# power_supply_module.net
KiCad netlist of a schematic drawn in EAGLE
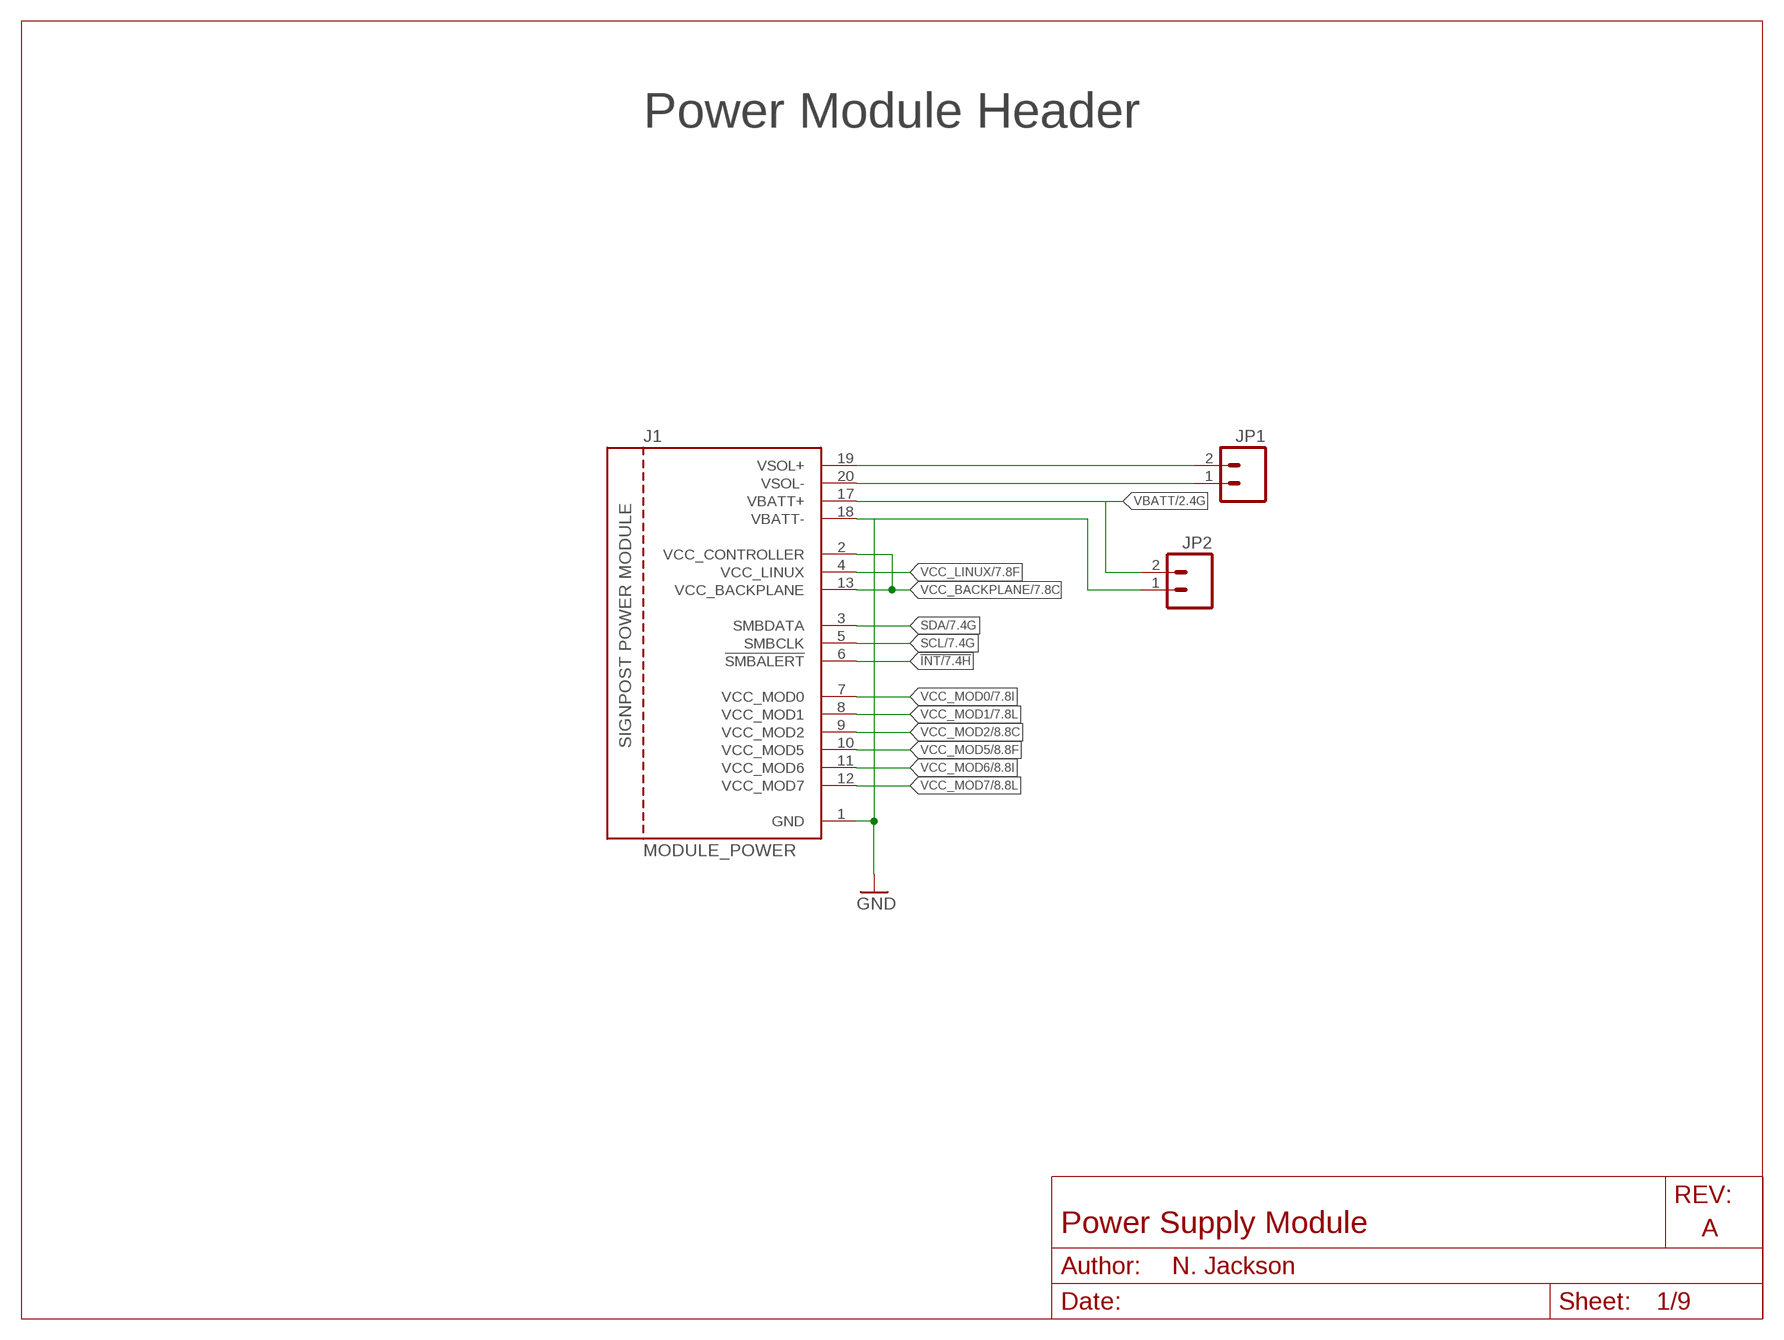
[diagram p0: schematic, sheet 1]
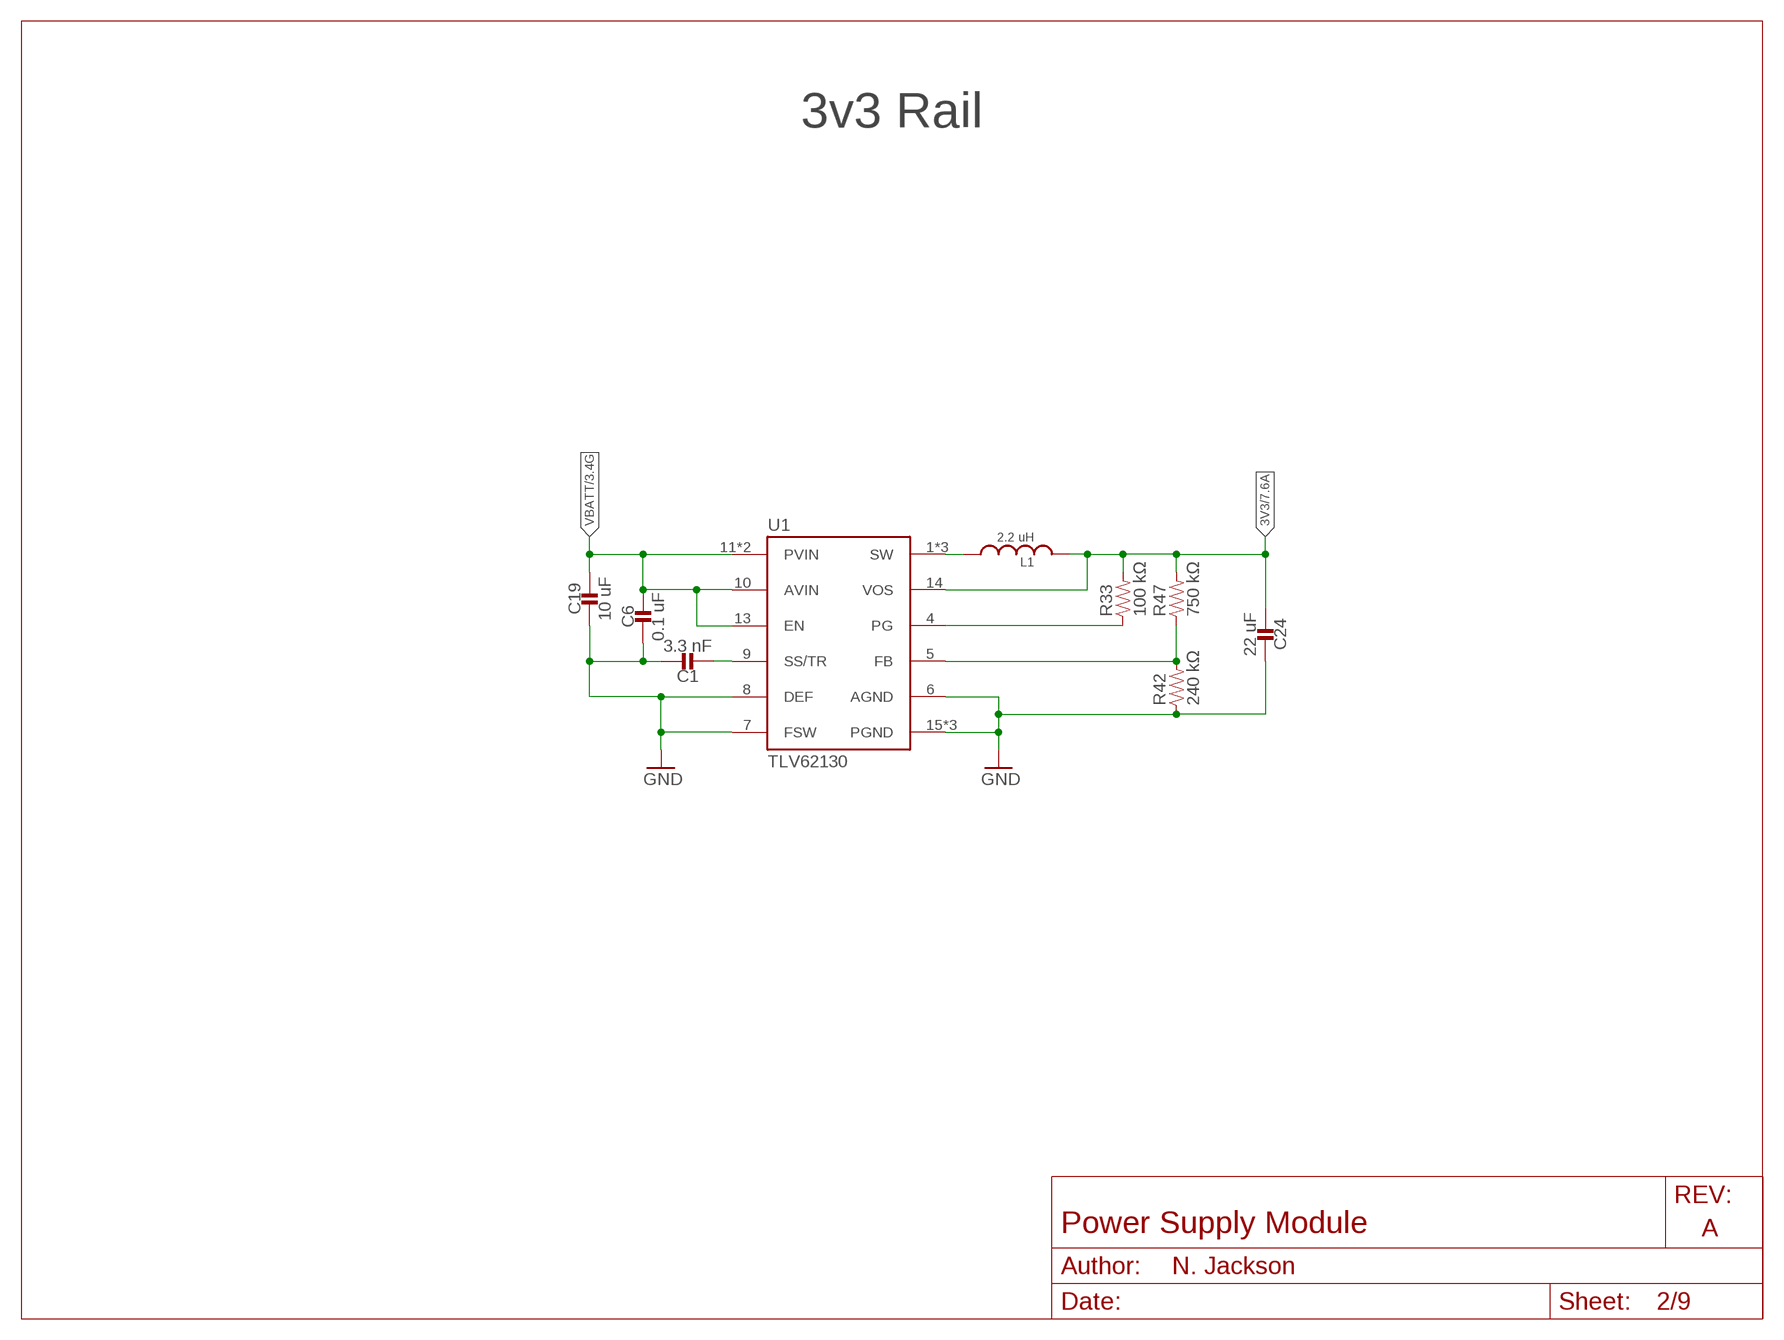
[diagram p1: schematic, sheet 2]
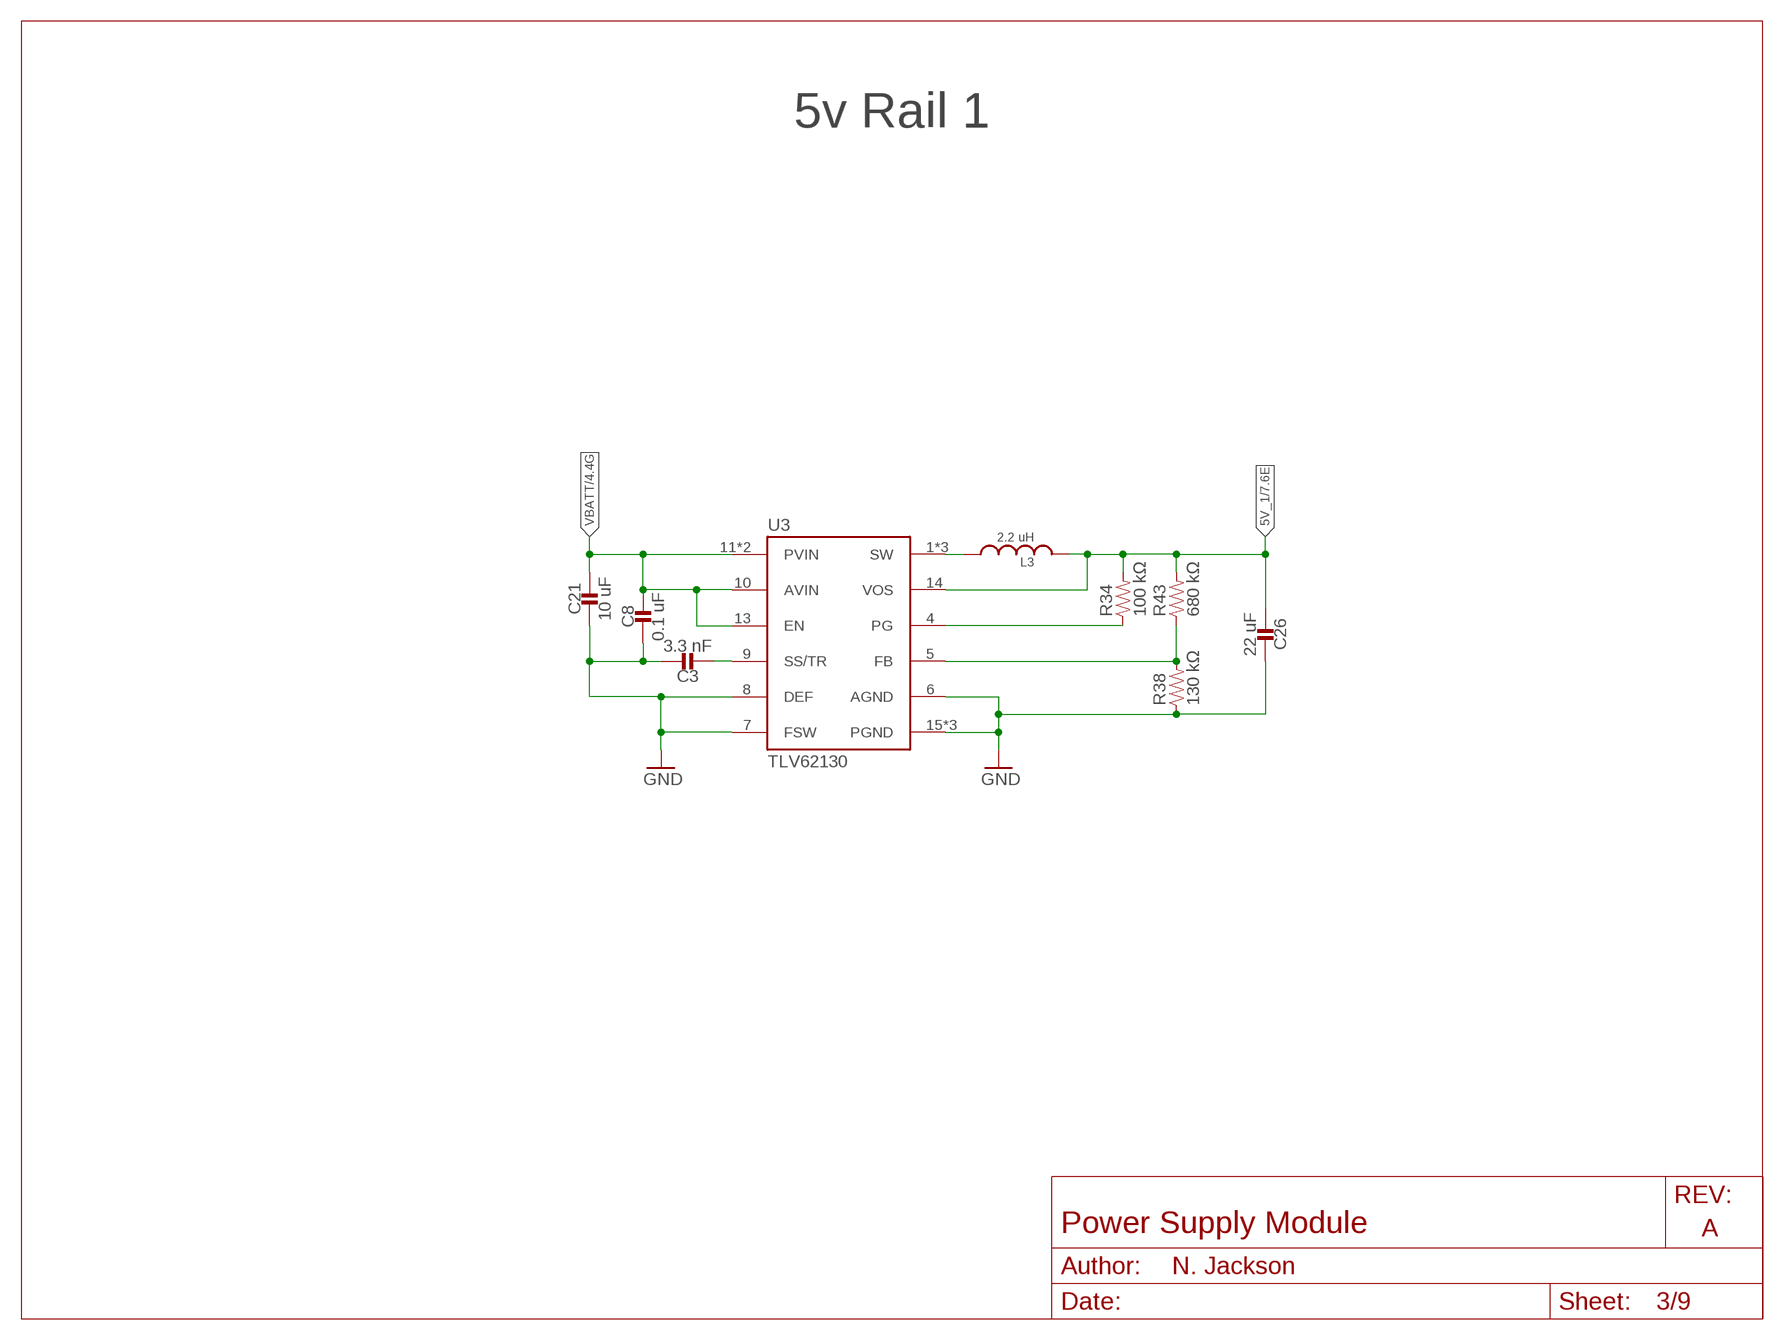
[diagram p2: schematic, sheet 3]
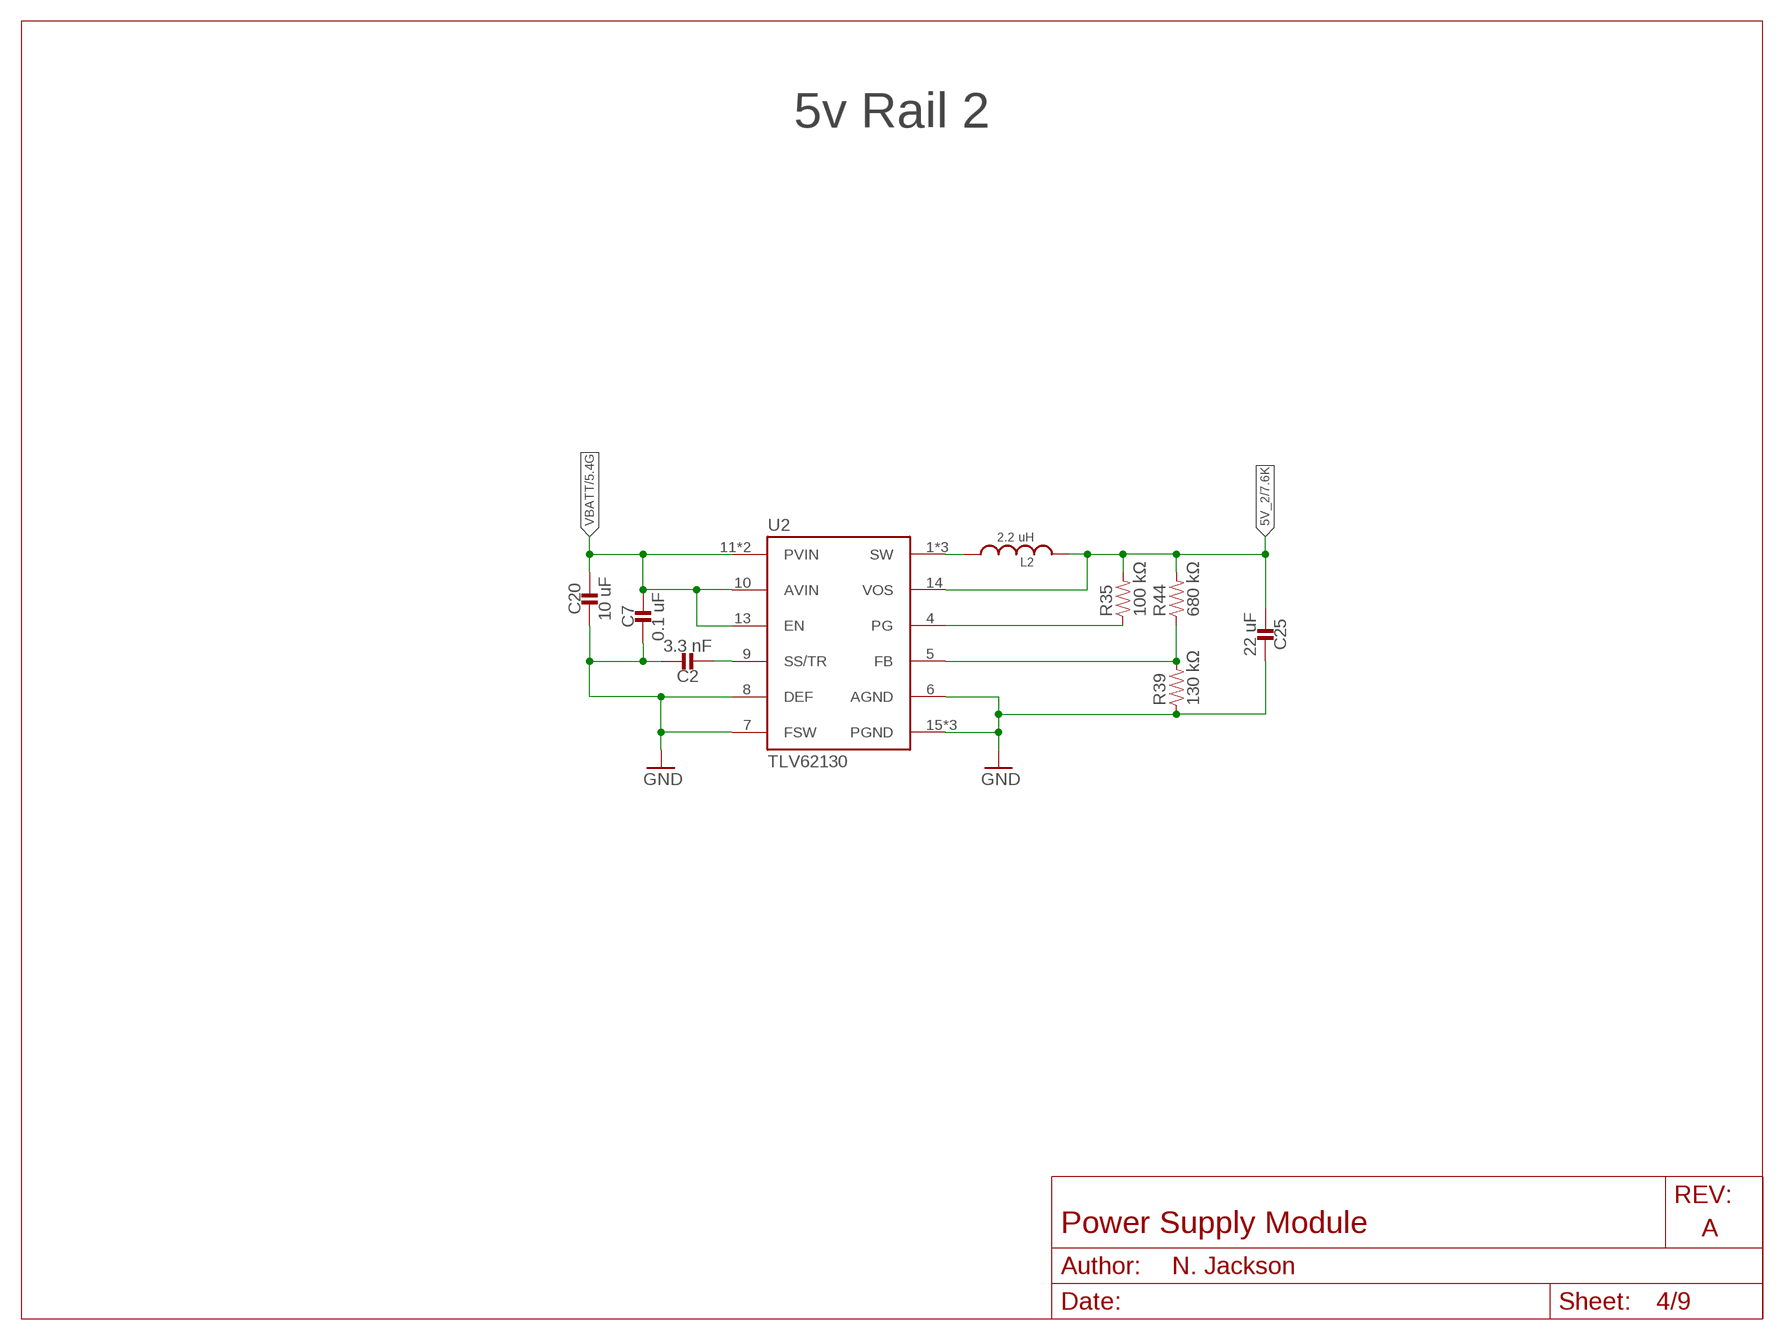
[diagram p3: schematic, sheet 4]
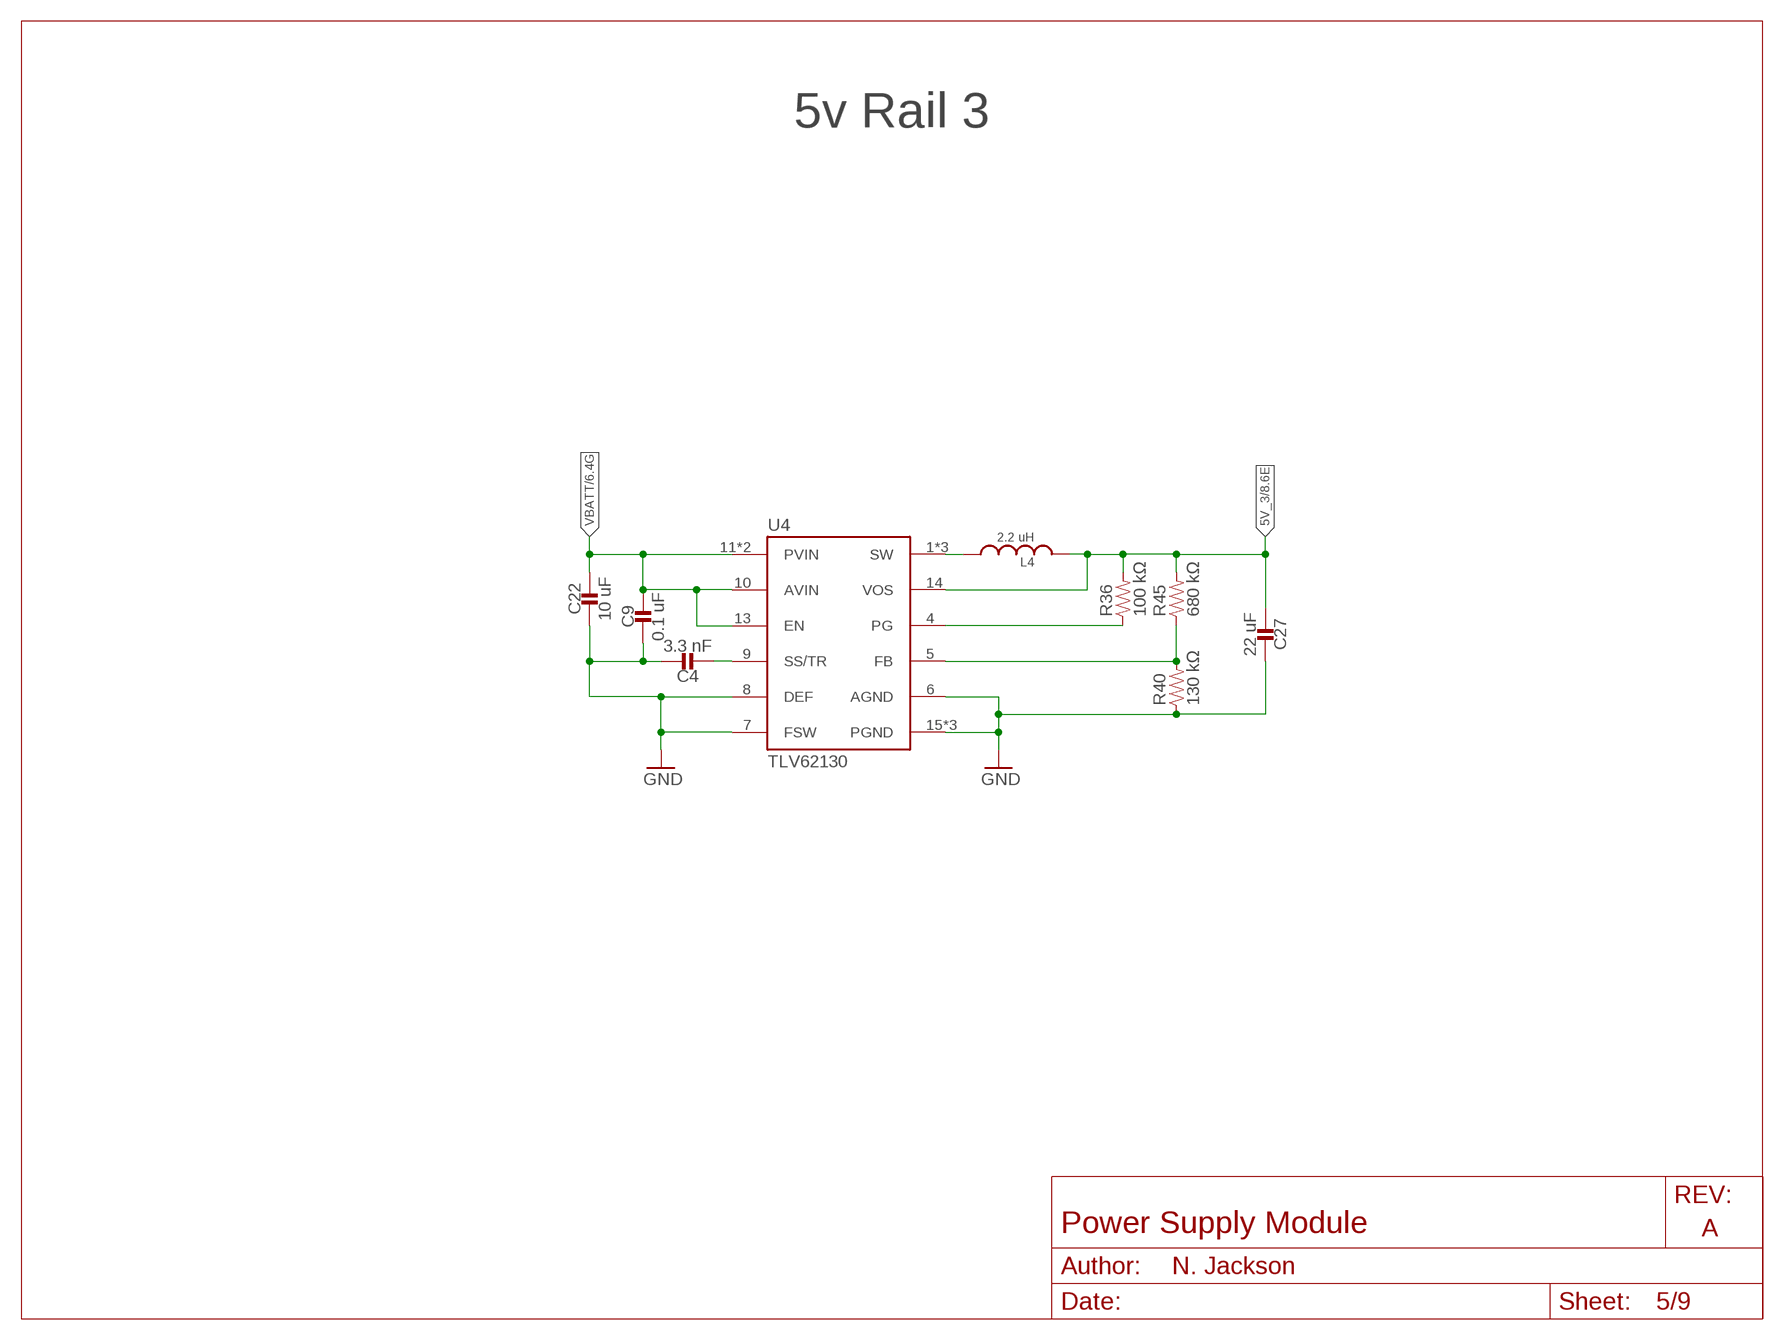
[diagram p4: schematic, sheet 5]
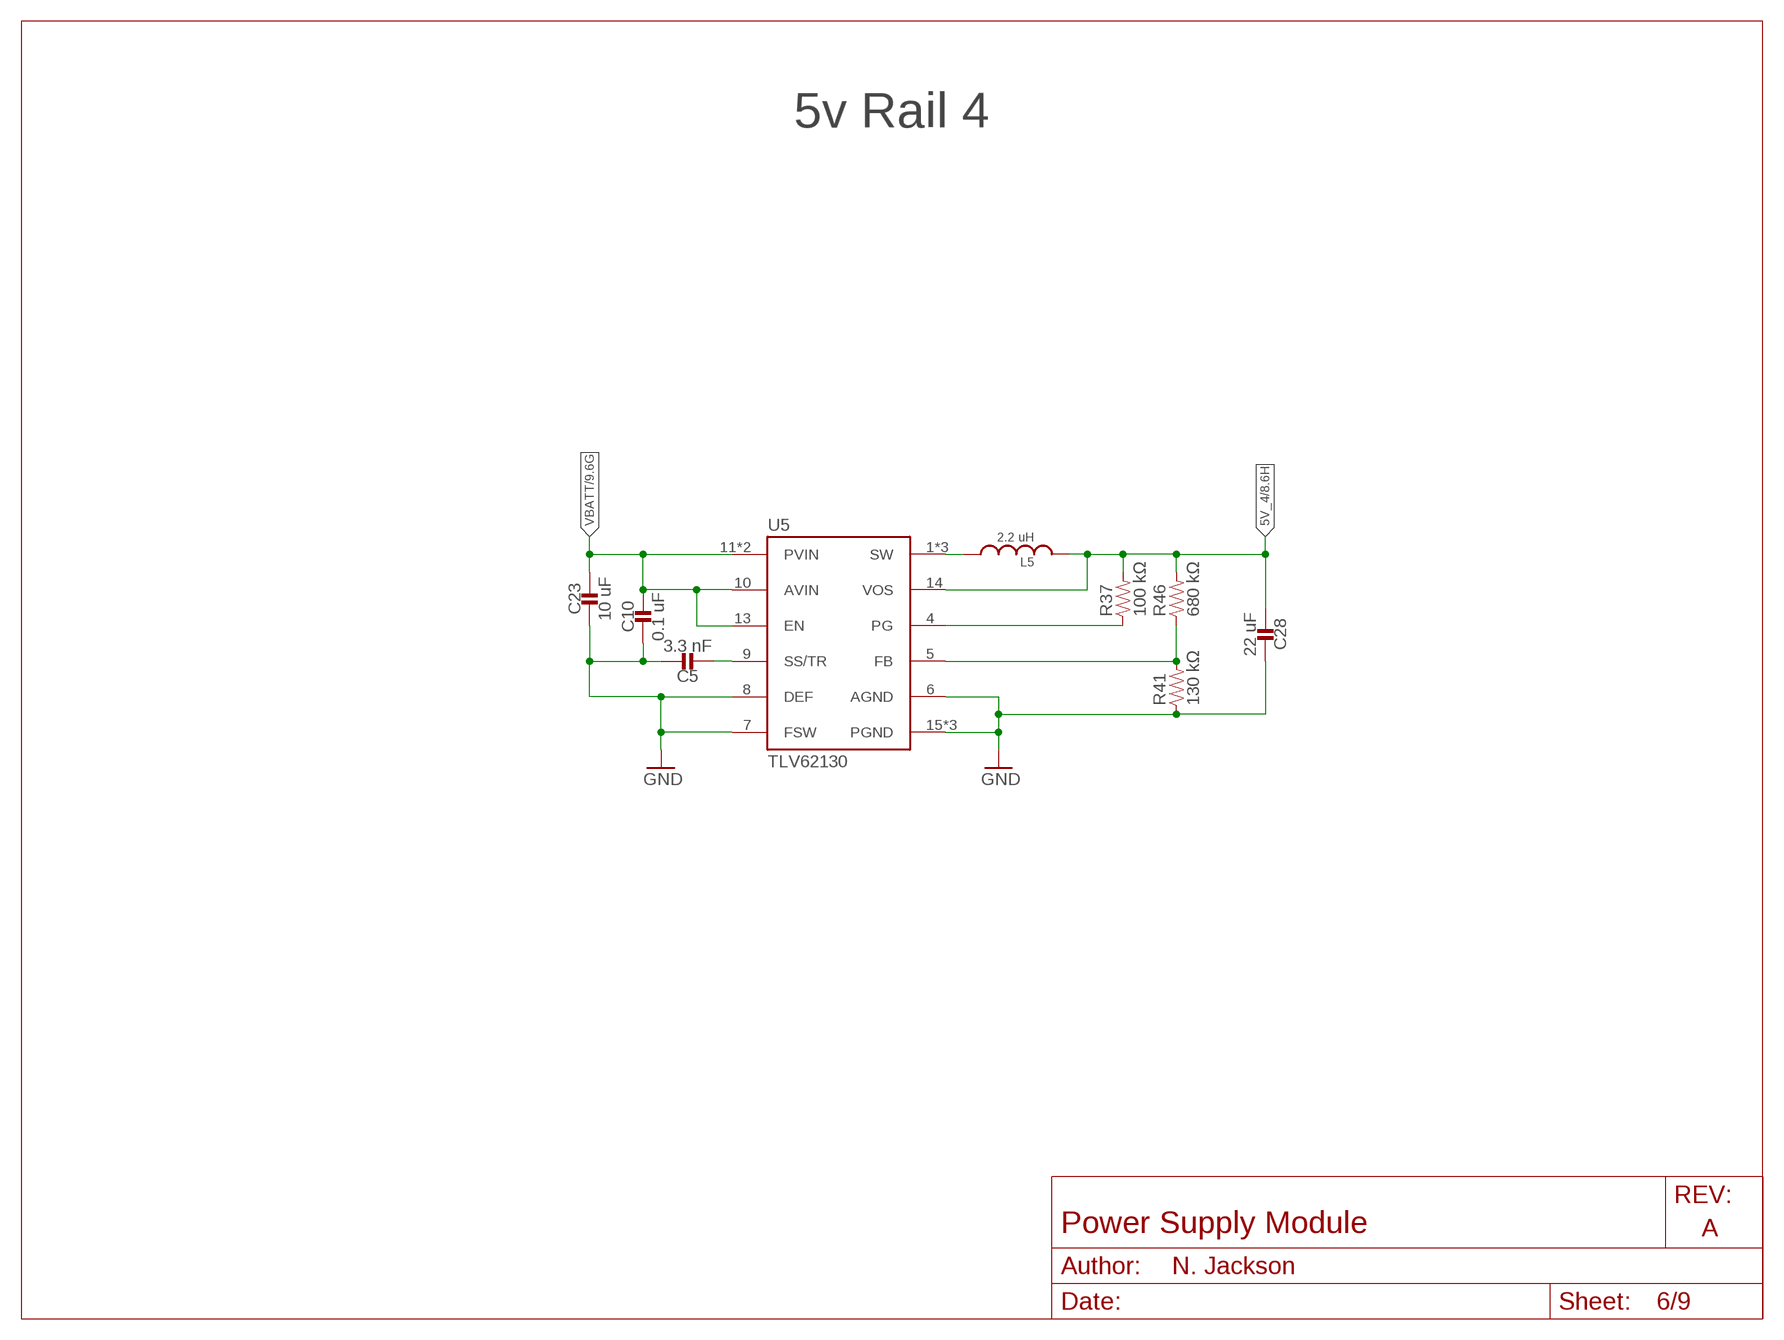
[diagram p5: schematic, sheet 6]
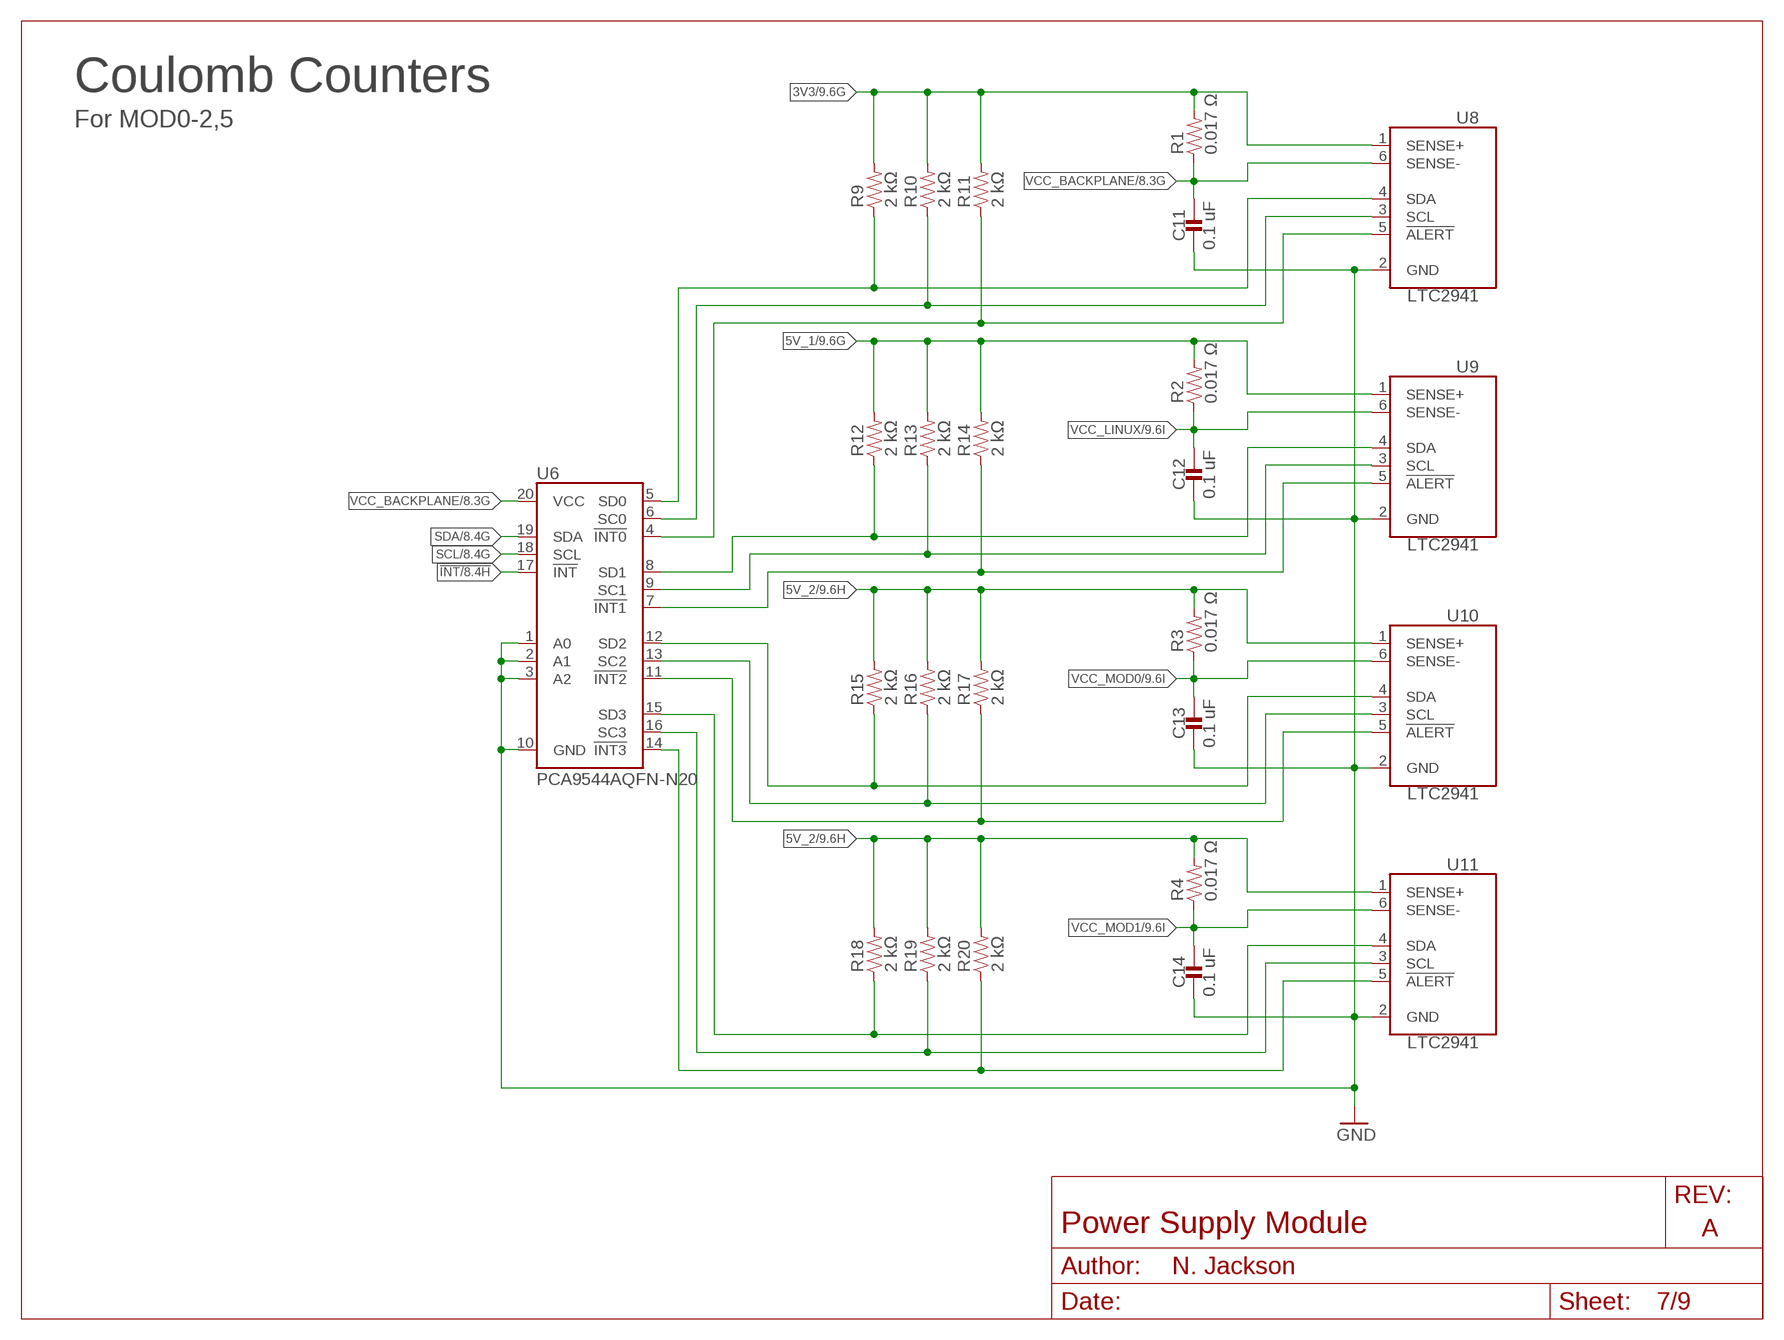
[diagram p6: schematic, sheet 7]
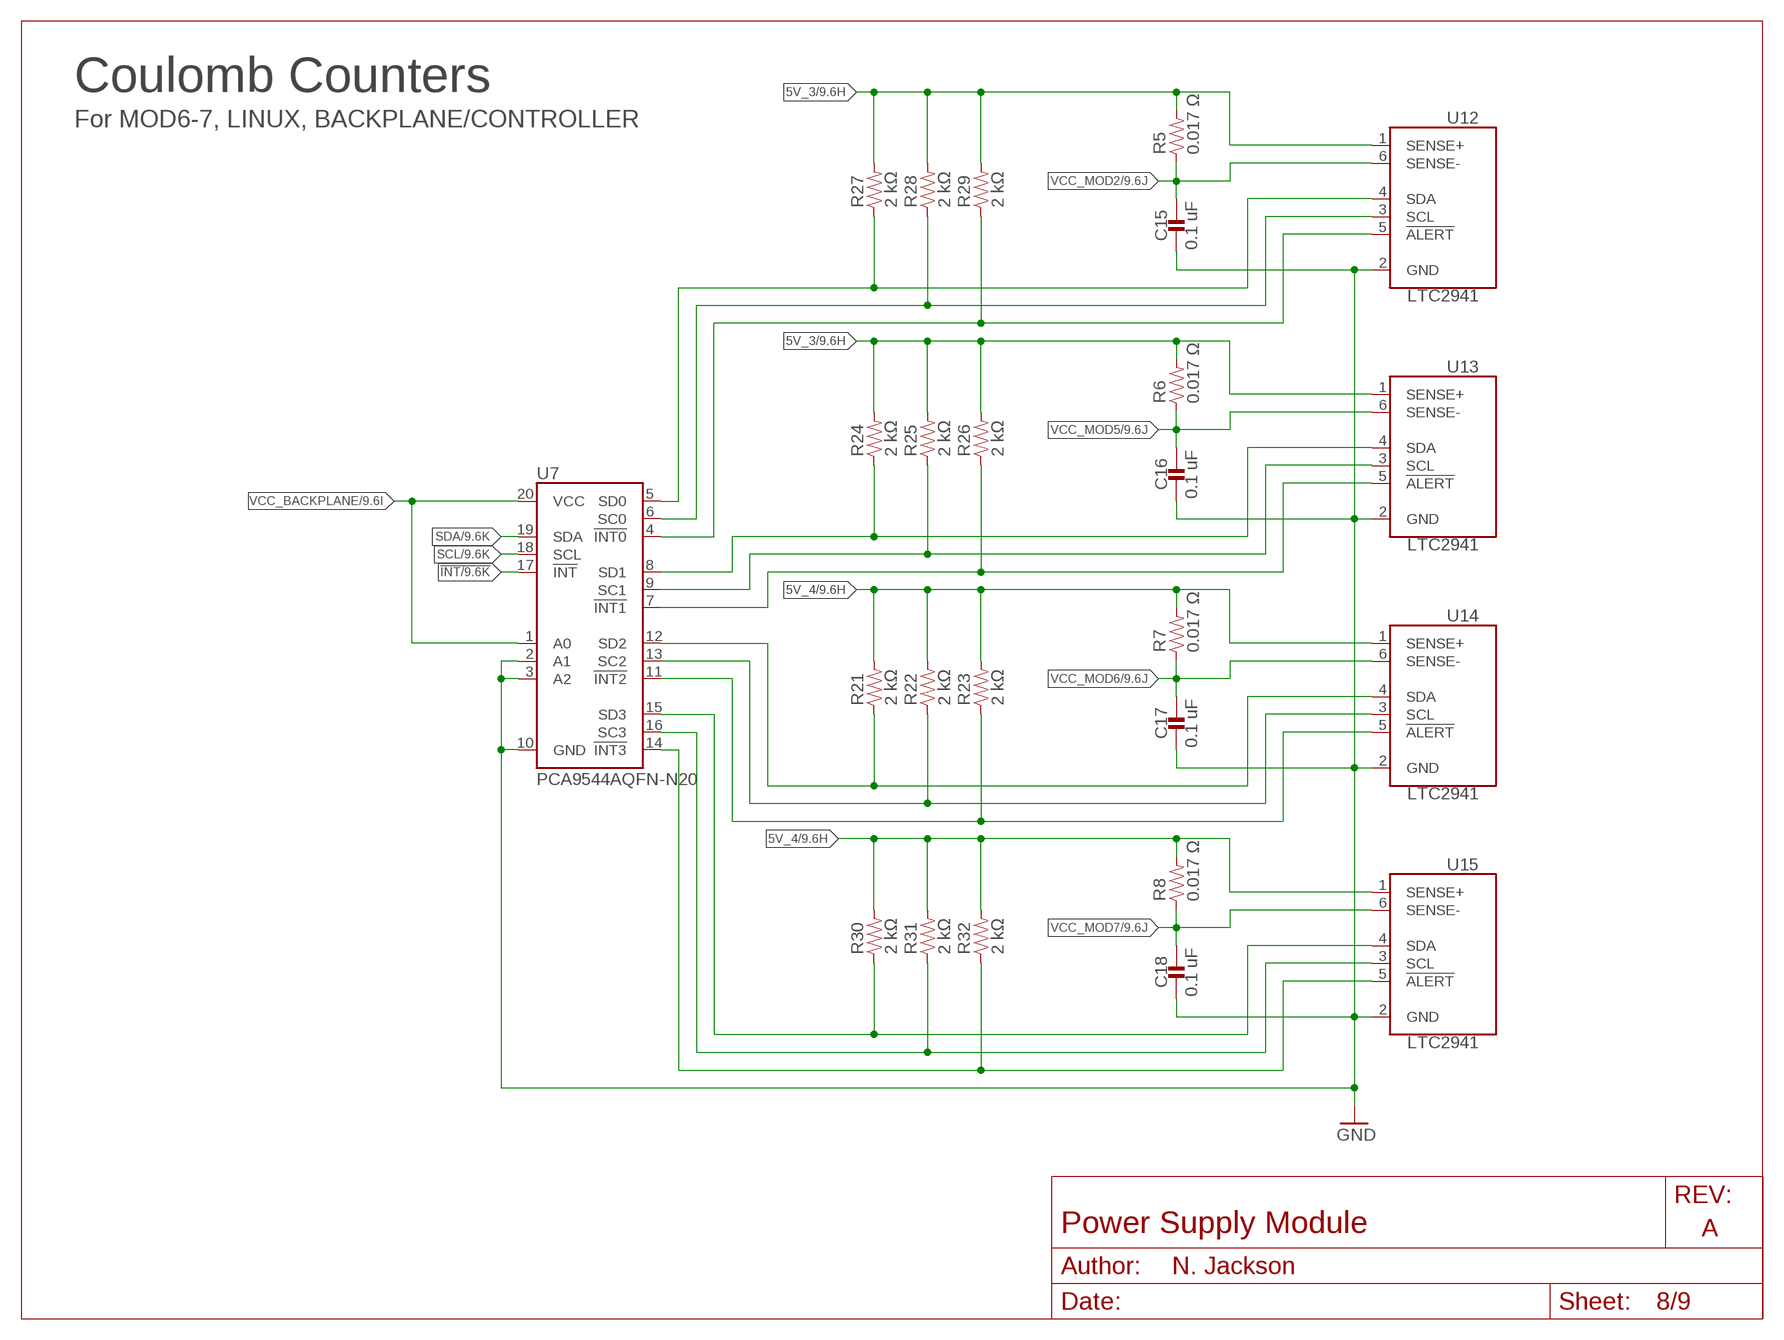
[diagram p7: schematic, sheet 8]
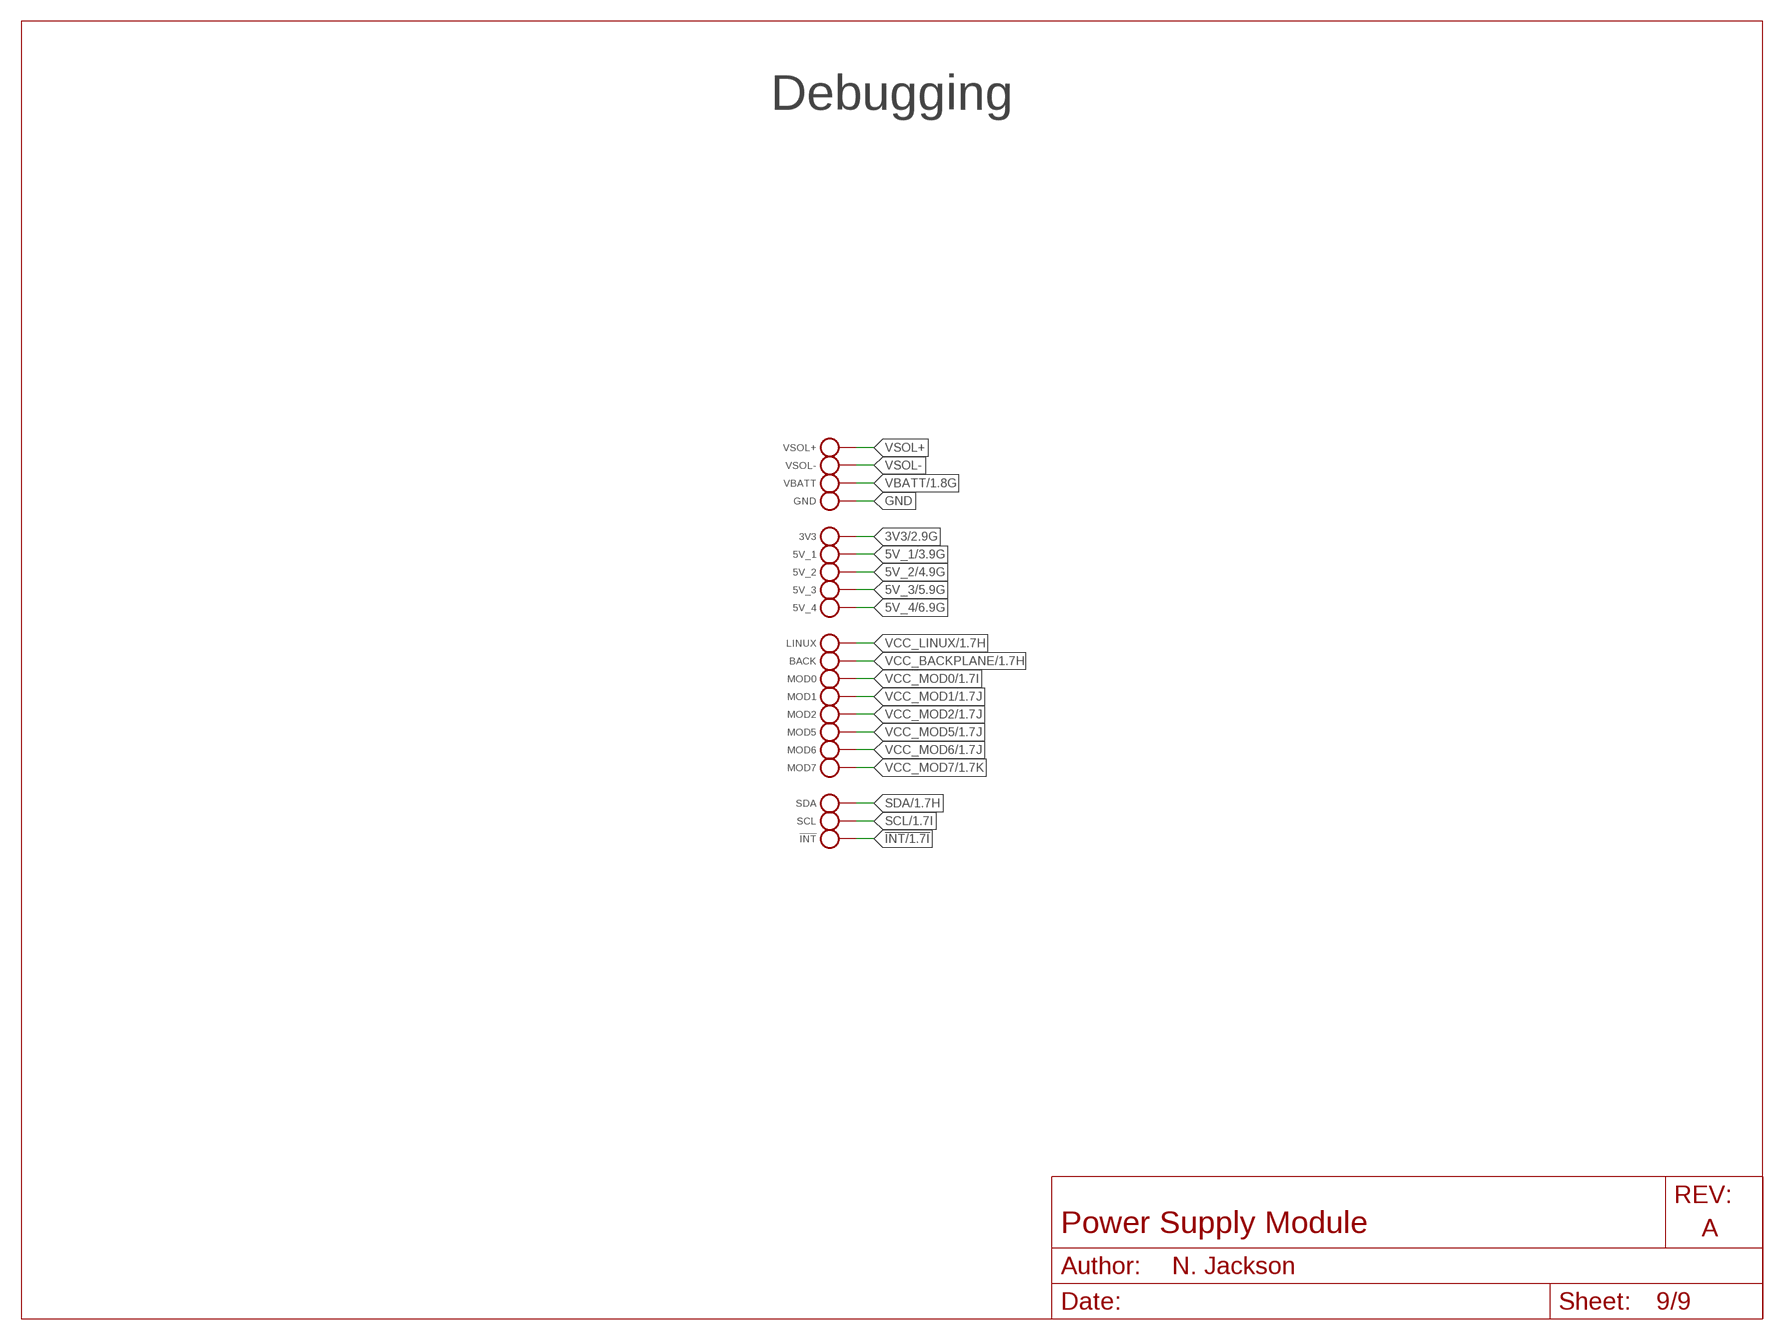
[diagram p8: schematic, sheet 9]

(export (version "E")
  (design (tool "Eeschema 10.0.6"))
  (components
    (comp (ref "C3")
      (value "3.3 nF")
      (footprint "eagle-import:0402_CAP")
      (libsource (lib "eagle-import") (part "CAPACITOR0402_CAP"))
    )
    (comp (ref "C8")
      (value "0.1 uF")
      (footprint "eagle-import:0402_CAP")
      (libsource (lib "eagle-import") (part "CAPACITOR0402_CAP"))
    )
    (comp (ref "C21")
      (value "10 uF")
      (footprint "eagle-import:0805_CAP")
      (libsource (lib "eagle-import") (part "CAPACITOR0805_CAP"))
    )
    (comp (ref "C26")
      (value "22 uF")
      (footprint "eagle-import:0603_CAP")
      (libsource (lib "eagle-import") (part "CAPACITOR0603_CAP"))
    )
    (comp (ref "L3")
      (value "2.2 uH")
      (footprint "eagle-import:IHL-1212BZ-11")
      (libsource (lib "eagle-import") (part "INDUCTORIHL"))
    )
    (comp (ref "R34")
      (value "100 kΩ")
      (footprint "eagle-import:0402_RES")
      (libsource (lib "eagle-import") (part "RESISTOR0402_RES"))
    )
    (comp (ref "R38")
      (value "130 kΩ")
      (footprint "eagle-import:0402_RES")
      (libsource (lib "eagle-import") (part "RESISTOR0402_RES"))
    )
    (comp (ref "R43")
      (value "680 kΩ")
      (footprint "eagle-import:0402_RES")
      (libsource (lib "eagle-import") (part "RESISTOR0402_RES"))
    )
    (comp (ref "U3")
      (value "TLV62130")
      (footprint "eagle-import:TQFN-16_3MM")
      (libsource (lib "eagle-import") (part "TLV62130"))
    )
    (comp (ref "!INT")
      (value "TEST_POINT_0.040IN")
      (footprint "eagle-import:TESTPOINT_0.040IN")
      (libsource (lib "eagle-import") (part "TEST_POINT_0.040IN"))
    )
    (comp (ref "3V3")
      (value "TEST_POINT_0.040IN")
      (footprint "eagle-import:TESTPOINT_0.040IN")
      (libsource (lib "eagle-import") (part "TEST_POINT_0.040IN"))
    )
    (comp (ref "5V_1")
      (value "TEST_POINT_0.040IN")
      (footprint "eagle-import:TESTPOINT_0.040IN")
      (libsource (lib "eagle-import") (part "TEST_POINT_0.040IN"))
    )
    (comp (ref "5V_2")
      (value "TEST_POINT_0.040IN")
      (footprint "eagle-import:TESTPOINT_0.040IN")
      (libsource (lib "eagle-import") (part "TEST_POINT_0.040IN"))
    )
    (comp (ref "5V_3")
      (value "TEST_POINT_0.040IN")
      (footprint "eagle-import:TESTPOINT_0.040IN")
      (libsource (lib "eagle-import") (part "TEST_POINT_0.040IN"))
    )
    (comp (ref "5V_4")
      (value "TEST_POINT_0.040IN")
      (footprint "eagle-import:TESTPOINT_0.040IN")
      (libsource (lib "eagle-import") (part "TEST_POINT_0.040IN"))
    )
    (comp (ref "BACK")
      (value "TEST_POINT_0.040IN")
      (footprint "eagle-import:TESTPOINT_0.040IN")
      (libsource (lib "eagle-import") (part "TEST_POINT_0.040IN"))
    )
    (comp (ref "GND")
      (value "TEST_POINT_0.040IN")
      (footprint "eagle-import:TESTPOINT_0.040IN")
      (libsource (lib "eagle-import") (part "TEST_POINT_0.040IN"))
    )
    (comp (ref "LINUX")
      (value "TEST_POINT_0.040IN")
      (footprint "eagle-import:TESTPOINT_0.040IN")
      (libsource (lib "eagle-import") (part "TEST_POINT_0.040IN"))
    )
    (comp (ref "MOD0")
      (value "TEST_POINT_0.040IN")
      (footprint "eagle-import:TESTPOINT_0.040IN")
      (libsource (lib "eagle-import") (part "TEST_POINT_0.040IN"))
    )
    (comp (ref "MOD1")
      (value "TEST_POINT_0.040IN")
      (footprint "eagle-import:TESTPOINT_0.040IN")
      (libsource (lib "eagle-import") (part "TEST_POINT_0.040IN"))
    )
    (comp (ref "MOD2")
      (value "TEST_POINT_0.040IN")
      (footprint "eagle-import:TESTPOINT_0.040IN")
      (libsource (lib "eagle-import") (part "TEST_POINT_0.040IN"))
    )
    (comp (ref "MOD5")
      (value "TEST_POINT_0.040IN")
      (footprint "eagle-import:TESTPOINT_0.040IN")
      (libsource (lib "eagle-import") (part "TEST_POINT_0.040IN"))
    )
    (comp (ref "MOD6")
      (value "TEST_POINT_0.040IN")
      (footprint "eagle-import:TESTPOINT_0.040IN")
      (libsource (lib "eagle-import") (part "TEST_POINT_0.040IN"))
    )
    (comp (ref "MOD7")
      (value "TEST_POINT_0.040IN")
      (footprint "eagle-import:TESTPOINT_0.040IN")
      (libsource (lib "eagle-import") (part "TEST_POINT_0.040IN"))
    )
    (comp (ref "SCL")
      (value "TEST_POINT_0.040IN")
      (footprint "eagle-import:TESTPOINT_0.040IN")
      (libsource (lib "eagle-import") (part "TEST_POINT_0.040IN"))
    )
    (comp (ref "SDA")
      (value "TEST_POINT_0.040IN")
      (footprint "eagle-import:TESTPOINT_0.040IN")
      (libsource (lib "eagle-import") (part "TEST_POINT_0.040IN"))
    )
    (comp (ref "VBATT")
      (value "TEST_POINT_0.040IN")
      (footprint "eagle-import:TESTPOINT_0.040IN")
      (libsource (lib "eagle-import") (part "TEST_POINT_0.040IN"))
    )
    (comp (ref "VSOL+")
      (value "TEST_POINT_0.040IN")
      (footprint "eagle-import:TESTPOINT_0.040IN")
      (libsource (lib "eagle-import") (part "TEST_POINT_0.040IN"))
    )
    (comp (ref "VSOL-")
      (value "TEST_POINT_0.040IN")
      (footprint "eagle-import:TESTPOINT_0.040IN")
      (libsource (lib "eagle-import") (part "TEST_POINT_0.040IN"))
    )
    (comp (ref "C11")
      (value "0.1 uF")
      (footprint "eagle-import:0402_CAP")
      (libsource (lib "eagle-import") (part "CAPACITOR0402_CAP"))
    )
    (comp (ref "C12")
      (value "0.1 uF")
      (footprint "eagle-import:0402_CAP")
      (libsource (lib "eagle-import") (part "CAPACITOR0402_CAP"))
    )
    (comp (ref "C13")
      (value "0.1 uF")
      (footprint "eagle-import:0402_CAP")
      (libsource (lib "eagle-import") (part "CAPACITOR0402_CAP"))
    )
    (comp (ref "C14")
      (value "0.1 uF")
      (footprint "eagle-import:0402_CAP")
      (libsource (lib "eagle-import") (part "CAPACITOR0402_CAP"))
    )
    (comp (ref "R1")
      (value "0.017 Ω")
      (footprint "eagle-import:0805_RES")
      (libsource (lib "eagle-import") (part "RESISTOR0805_RES"))
    )
    (comp (ref "R2")
      (value "0.017 Ω")
      (footprint "eagle-import:0805_RES")
      (libsource (lib "eagle-import") (part "RESISTOR0805_RES"))
    )
    (comp (ref "R3")
      (value "0.017 Ω")
      (footprint "eagle-import:0805_RES")
      (libsource (lib "eagle-import") (part "RESISTOR0805_RES"))
    )
    (comp (ref "R4")
      (value "0.017 Ω")
      (footprint "eagle-import:0805_RES")
      (libsource (lib "eagle-import") (part "RESISTOR0805_RES"))
    )
    (comp (ref "R9")
      (value "2 kΩ")
      (footprint "eagle-import:0402_RES")
      (libsource (lib "eagle-import") (part "RESISTOR0402_RES"))
    )
    (comp (ref "R10")
      (value "2 kΩ")
      (footprint "eagle-import:0402_RES")
      (libsource (lib "eagle-import") (part "RESISTOR0402_RES"))
    )
    (comp (ref "R11")
      (value "2 kΩ")
      (footprint "eagle-import:0402_RES")
      (libsource (lib "eagle-import") (part "RESISTOR0402_RES"))
    )
    (comp (ref "R12")
      (value "2 kΩ")
      (footprint "eagle-import:0402_RES")
      (libsource (lib "eagle-import") (part "RESISTOR0402_RES"))
    )
    (comp (ref "R13")
      (value "2 kΩ")
      (footprint "eagle-import:0402_RES")
      (libsource (lib "eagle-import") (part "RESISTOR0402_RES"))
    )
    (comp (ref "R14")
      (value "2 kΩ")
      (footprint "eagle-import:0402_RES")
      (libsource (lib "eagle-import") (part "RESISTOR0402_RES"))
    )
    (comp (ref "R15")
      (value "2 kΩ")
      (footprint "eagle-import:0402_RES")
      (libsource (lib "eagle-import") (part "RESISTOR0402_RES"))
    )
    (comp (ref "R16")
      (value "2 kΩ")
      (footprint "eagle-import:0402_RES")
      (libsource (lib "eagle-import") (part "RESISTOR0402_RES"))
    )
    (comp (ref "R17")
      (value "2 kΩ")
      (footprint "eagle-import:0402_RES")
      (libsource (lib "eagle-import") (part "RESISTOR0402_RES"))
    )
    (comp (ref "R18")
      (value "2 kΩ")
      (footprint "eagle-import:0402_RES")
      (libsource (lib "eagle-import") (part "RESISTOR0402_RES"))
    )
    (comp (ref "R19")
      (value "2 kΩ")
      (footprint "eagle-import:0402_RES")
      (libsource (lib "eagle-import") (part "RESISTOR0402_RES"))
    )
    (comp (ref "R20")
      (value "2 kΩ")
      (footprint "eagle-import:0402_RES")
      (libsource (lib "eagle-import") (part "RESISTOR0402_RES"))
    )
    (comp (ref "U6")
      (value "PCA9544AQFN-N20")
      (footprint "eagle-import:QFN-N20")
      (libsource (lib "eagle-import") (part "PCA9544AQFN-N20"))
    )
    (comp (ref "U8")
      (value "LTC2941")
      (footprint "eagle-import:DFN-6-2MMX3MM")
      (libsource (lib "eagle-import") (part "LTC2941"))
    )
    (comp (ref "U9")
      (value "LTC2941")
      (footprint "eagle-import:DFN-6-2MMX3MM")
      (libsource (lib "eagle-import") (part "LTC2941"))
    )
    (comp (ref "U10")
      (value "LTC2941")
      (footprint "eagle-import:DFN-6-2MMX3MM")
      (libsource (lib "eagle-import") (part "LTC2941"))
    )
    (comp (ref "U11")
      (value "LTC2941")
      (footprint "eagle-import:DFN-6-2MMX3MM")
      (libsource (lib "eagle-import") (part "LTC2941"))
    )
    (comp (ref "C4")
      (value "3.3 nF")
      (footprint "eagle-import:0402_CAP")
      (libsource (lib "eagle-import") (part "CAPACITOR0402_CAP"))
    )
    (comp (ref "C9")
      (value "0.1 uF")
      (footprint "eagle-import:0402_CAP")
      (libsource (lib "eagle-import") (part "CAPACITOR0402_CAP"))
    )
    (comp (ref "C22")
      (value "10 uF")
      (footprint "eagle-import:0805_CAP")
      (libsource (lib "eagle-import") (part "CAPACITOR0805_CAP"))
    )
    (comp (ref "C27")
      (value "22 uF")
      (footprint "eagle-import:0603_CAP")
      (libsource (lib "eagle-import") (part "CAPACITOR0603_CAP"))
    )
    (comp (ref "L4")
      (value "2.2 uH")
      (footprint "eagle-import:IHL-1212BZ-11")
      (libsource (lib "eagle-import") (part "INDUCTORIHL"))
    )
    (comp (ref "R36")
      (value "100 kΩ")
      (footprint "eagle-import:0402_RES")
      (libsource (lib "eagle-import") (part "RESISTOR0402_RES"))
    )
    (comp (ref "R40")
      (value "130 kΩ")
      (footprint "eagle-import:0402_RES")
      (libsource (lib "eagle-import") (part "RESISTOR0402_RES"))
    )
    (comp (ref "R45")
      (value "680 kΩ")
      (footprint "eagle-import:0402_RES")
      (libsource (lib "eagle-import") (part "RESISTOR0402_RES"))
    )
    (comp (ref "U4")
      (value "TLV62130")
      (footprint "eagle-import:TQFN-16_3MM")
      (libsource (lib "eagle-import") (part "TLV62130"))
    )
    (comp (ref "C15")
      (value "0.1 uF")
      (footprint "eagle-import:0402_CAP")
      (libsource (lib "eagle-import") (part "CAPACITOR0402_CAP"))
    )
    (comp (ref "C16")
      (value "0.1 uF")
      (footprint "eagle-import:0402_CAP")
      (libsource (lib "eagle-import") (part "CAPACITOR0402_CAP"))
    )
    (comp (ref "C17")
      (value "0.1 uF")
      (footprint "eagle-import:0402_CAP")
      (libsource (lib "eagle-import") (part "CAPACITOR0402_CAP"))
    )
    (comp (ref "C18")
      (value "0.1 uF")
      (footprint "eagle-import:0402_CAP")
      (libsource (lib "eagle-import") (part "CAPACITOR0402_CAP"))
    )
    (comp (ref "R5")
      (value "0.017 Ω")
      (footprint "eagle-import:0805_RES")
      (libsource (lib "eagle-import") (part "RESISTOR0805_RES"))
    )
    (comp (ref "R6")
      (value "0.017 Ω")
      (footprint "eagle-import:0805_RES")
      (libsource (lib "eagle-import") (part "RESISTOR0805_RES"))
    )
    (comp (ref "R7")
      (value "0.017 Ω")
      (footprint "eagle-import:0805_RES")
      (libsource (lib "eagle-import") (part "RESISTOR0805_RES"))
    )
    (comp (ref "R8")
      (value "0.017 Ω")
      (footprint "eagle-import:0805_RES")
      (libsource (lib "eagle-import") (part "RESISTOR0805_RES"))
    )
    (comp (ref "R21")
      (value "2 kΩ")
      (footprint "eagle-import:0402_RES")
      (libsource (lib "eagle-import") (part "RESISTOR0402_RES"))
    )
    (comp (ref "R22")
      (value "2 kΩ")
      (footprint "eagle-import:0402_RES")
      (libsource (lib "eagle-import") (part "RESISTOR0402_RES"))
    )
    (comp (ref "R23")
      (value "2 kΩ")
      (footprint "eagle-import:0402_RES")
      (libsource (lib "eagle-import") (part "RESISTOR0402_RES"))
    )
    (comp (ref "R24")
      (value "2 kΩ")
      (footprint "eagle-import:0402_RES")
      (libsource (lib "eagle-import") (part "RESISTOR0402_RES"))
    )
    (comp (ref "R25")
      (value "2 kΩ")
      (footprint "eagle-import:0402_RES")
      (libsource (lib "eagle-import") (part "RESISTOR0402_RES"))
    )
    (comp (ref "R26")
      (value "2 kΩ")
      (footprint "eagle-import:0402_RES")
      (libsource (lib "eagle-import") (part "RESISTOR0402_RES"))
    )
    (comp (ref "R27")
      (value "2 kΩ")
      (footprint "eagle-import:0402_RES")
      (libsource (lib "eagle-import") (part "RESISTOR0402_RES"))
    )
    (comp (ref "R28")
      (value "2 kΩ")
      (footprint "eagle-import:0402_RES")
      (libsource (lib "eagle-import") (part "RESISTOR0402_RES"))
    )
    (comp (ref "R29")
      (value "2 kΩ")
      (footprint "eagle-import:0402_RES")
      (libsource (lib "eagle-import") (part "RESISTOR0402_RES"))
    )
    (comp (ref "R30")
      (value "2 kΩ")
      (footprint "eagle-import:0402_RES")
      (libsource (lib "eagle-import") (part "RESISTOR0402_RES"))
    )
    (comp (ref "R31")
      (value "2 kΩ")
      (footprint "eagle-import:0402_RES")
      (libsource (lib "eagle-import") (part "RESISTOR0402_RES"))
    )
    (comp (ref "R32")
      (value "2 kΩ")
      (footprint "eagle-import:0402_RES")
      (libsource (lib "eagle-import") (part "RESISTOR0402_RES"))
    )
    (comp (ref "U7")
      (value "PCA9544AQFN-N20")
      (footprint "eagle-import:QFN-N20")
      (libsource (lib "eagle-import") (part "PCA9544AQFN-N20"))
    )
    (comp (ref "U12")
      (value "LTC2941")
      (footprint "eagle-import:DFN-6-2MMX3MM")
      (libsource (lib "eagle-import") (part "LTC2941"))
    )
    (comp (ref "U13")
      (value "LTC2941")
      (footprint "eagle-import:DFN-6-2MMX3MM")
      (libsource (lib "eagle-import") (part "LTC2941"))
    )
    (comp (ref "U14")
      (value "LTC2941")
      (footprint "eagle-import:DFN-6-2MMX3MM")
      (libsource (lib "eagle-import") (part "LTC2941"))
    )
    (comp (ref "U15")
      (value "LTC2941")
      (footprint "eagle-import:DFN-6-2MMX3MM")
      (libsource (lib "eagle-import") (part "LTC2941"))
    )
    (comp (ref "C5")
      (value "3.3 nF")
      (footprint "eagle-import:0402_CAP")
      (libsource (lib "eagle-import") (part "CAPACITOR0402_CAP"))
    )
    (comp (ref "C10")
      (value "0.1 uF")
      (footprint "eagle-import:0402_CAP")
      (libsource (lib "eagle-import") (part "CAPACITOR0402_CAP"))
    )
    (comp (ref "C23")
      (value "10 uF")
      (footprint "eagle-import:0805_CAP")
      (libsource (lib "eagle-import") (part "CAPACITOR0805_CAP"))
    )
    (comp (ref "C28")
      (value "22 uF")
      (footprint "eagle-import:0603_CAP")
      (libsource (lib "eagle-import") (part "CAPACITOR0603_CAP"))
    )
    (comp (ref "L5")
      (value "2.2 uH")
      (footprint "eagle-import:IHL-1212BZ-11")
      (libsource (lib "eagle-import") (part "INDUCTORIHL"))
    )
    (comp (ref "R37")
      (value "100 kΩ")
      (footprint "eagle-import:0402_RES")
      (libsource (lib "eagle-import") (part "RESISTOR0402_RES"))
    )
    (comp (ref "R41")
      (value "130 kΩ")
      (footprint "eagle-import:0402_RES")
      (libsource (lib "eagle-import") (part "RESISTOR0402_RES"))
    )
    (comp (ref "R46")
      (value "680 kΩ")
      (footprint "eagle-import:0402_RES")
      (libsource (lib "eagle-import") (part "RESISTOR0402_RES"))
    )
    (comp (ref "U5")
      (value "TLV62130")
      (footprint "eagle-import:TQFN-16_3MM")
      (libsource (lib "eagle-import") (part "TLV62130"))
    )
    (comp (ref "C1")
      (value "3.3 nF")
      (footprint "eagle-import:0402_CAP")
      (libsource (lib "eagle-import") (part "CAPACITOR0402_CAP"))
    )
    (comp (ref "C6")
      (value "0.1 uF")
      (footprint "eagle-import:0402_CAP")
      (libsource (lib "eagle-import") (part "CAPACITOR0402_CAP"))
    )
    (comp (ref "C19")
      (value "10 uF")
      (footprint "eagle-import:0805_CAP")
      (libsource (lib "eagle-import") (part "CAPACITOR0805_CAP"))
    )
    (comp (ref "C24")
      (value "22 uF")
      (footprint "eagle-import:0603_CAP")
      (libsource (lib "eagle-import") (part "CAPACITOR0603_CAP"))
    )
    (comp (ref "L1")
      (value "2.2 uH")
      (footprint "eagle-import:IHL-1212BZ-11")
      (libsource (lib "eagle-import") (part "INDUCTORIHL"))
    )
    (comp (ref "R33")
      (value "100 kΩ")
      (footprint "eagle-import:0402_RES")
      (libsource (lib "eagle-import") (part "RESISTOR0402_RES"))
    )
    (comp (ref "R42")
      (value "240 kΩ")
      (footprint "eagle-import:0402_RES")
      (libsource (lib "eagle-import") (part "RESISTOR0402_RES"))
    )
    (comp (ref "R47")
      (value "750 kΩ")
      (footprint "eagle-import:0402_RES")
      (libsource (lib "eagle-import") (part "RESISTOR0402_RES"))
    )
    (comp (ref "U1")
      (value "TLV62130")
      (footprint "eagle-import:TQFN-16_3MM")
      (libsource (lib "eagle-import") (part "TLV62130"))
    )
    (comp (ref "C2")
      (value "3.3 nF")
      (footprint "eagle-import:0402_CAP")
      (libsource (lib "eagle-import") (part "CAPACITOR0402_CAP"))
    )
    (comp (ref "C7")
      (value "0.1 uF")
      (footprint "eagle-import:0402_CAP")
      (libsource (lib "eagle-import") (part "CAPACITOR0402_CAP"))
    )
    (comp (ref "C20")
      (value "10 uF")
      (footprint "eagle-import:0805_CAP")
      (libsource (lib "eagle-import") (part "CAPACITOR0805_CAP"))
    )
    (comp (ref "C25")
      (value "22 uF")
      (footprint "eagle-import:0603_CAP")
      (libsource (lib "eagle-import") (part "CAPACITOR0603_CAP"))
    )
    (comp (ref "L2")
      (value "2.2 uH")
      (footprint "eagle-import:IHL-1212BZ-11")
      (libsource (lib "eagle-import") (part "INDUCTORIHL"))
    )
    (comp (ref "R35")
      (value "100 kΩ")
      (footprint "eagle-import:0402_RES")
      (libsource (lib "eagle-import") (part "RESISTOR0402_RES"))
    )
    (comp (ref "R39")
      (value "130 kΩ")
      (footprint "eagle-import:0402_RES")
      (libsource (lib "eagle-import") (part "RESISTOR0402_RES"))
    )
    (comp (ref "R44")
      (value "680 kΩ")
      (footprint "eagle-import:0402_RES")
      (libsource (lib "eagle-import") (part "RESISTOR0402_RES"))
    )
    (comp (ref "U2")
      (value "TLV62130")
      (footprint "eagle-import:TQFN-16_3MM")
      (libsource (lib "eagle-import") (part "TLV62130"))
    )
    (comp (ref "J1")
      (value "MODULE_POWER")
      (footprint "eagle-import:MODULE_POWER")
      (libsource (lib "eagle-import") (part "MODULE_POWER"))
    )
    (comp (ref "JP1")
      (value "M02PTH")
      (footprint "eagle-import:1X02")
      (libsource (lib "eagle-import") (part "M02PTH"))
    )
    (comp (ref "JP2")
      (value "M02PTH")
      (footprint "eagle-import:1X02")
      (libsource (lib "eagle-import") (part "M02PTH"))
    )
  )
  (nets
    (net (code "1") (name "3V3") (class "Default")
      (node (ref "3V3") (pin "TESTPOINT") (pinfunction "TESTPOINT_TESTPOINT") (pintype "bidirectional"))
      (node (ref "C24") (pin "2") (pinfunction "2_2") (pintype "bidirectional"))
      (node (ref "L1") (pin "P$2") (pinfunction "2_P$2") (pintype "bidirectional"))
      (node (ref "R1") (pin "2") (pinfunction "2_2") (pintype "passive"))
      (node (ref "R10") (pin "2") (pinfunction "2_2") (pintype "passive"))
      (node (ref "R11") (pin "2") (pinfunction "2_2") (pintype "passive"))
      (node (ref "R33") (pin "2") (pinfunction "2_2") (pintype "passive"))
      (node (ref "R47") (pin "2") (pinfunction "2_2") (pintype "passive"))
      (node (ref "R9") (pin "2") (pinfunction "2_2") (pintype "passive"))
      (node (ref "U1") (pin "14") (pinfunction "VOS_14") (pintype "bidirectional"))
      (node (ref "U8") (pin "1") (pinfunction "SENSE+_1") (pintype "open_collector"))
    )
    (net (code "2") (name "5V_1") (class "Default")
      (node (ref "5V_1") (pin "TESTPOINT") (pinfunction "TESTPOINT_TESTPOINT") (pintype "bidirectional"))
      (node (ref "C26") (pin "2") (pinfunction "2_2") (pintype "bidirectional"))
      (node (ref "L3") (pin "P$2") (pinfunction "2_P$2") (pintype "bidirectional"))
      (node (ref "R12") (pin "2") (pinfunction "2_2") (pintype "passive"))
      (node (ref "R13") (pin "2") (pinfunction "2_2") (pintype "passive"))
      (node (ref "R14") (pin "2") (pinfunction "2_2") (pintype "passive"))
      (node (ref "R2") (pin "2") (pinfunction "2_2") (pintype "passive"))
      (node (ref "R34") (pin "2") (pinfunction "2_2") (pintype "passive"))
      (node (ref "R43") (pin "2") (pinfunction "2_2") (pintype "passive"))
      (node (ref "U3") (pin "14") (pinfunction "VOS_14") (pintype "bidirectional"))
      (node (ref "U9") (pin "1") (pinfunction "SENSE+_1") (pintype "open_collector"))
    )
    (net (code "3") (name "5V_2") (class "Default")
      (node (ref "5V_2") (pin "TESTPOINT") (pinfunction "TESTPOINT_TESTPOINT") (pintype "bidirectional"))
      (node (ref "C25") (pin "2") (pinfunction "2_2") (pintype "bidirectional"))
      (node (ref "L2") (pin "P$2") (pinfunction "2_P$2") (pintype "bidirectional"))
      (node (ref "R15") (pin "2") (pinfunction "2_2") (pintype "passive"))
      (node (ref "R16") (pin "2") (pinfunction "2_2") (pintype "passive"))
      (node (ref "R17") (pin "2") (pinfunction "2_2") (pintype "passive"))
      (node (ref "R18") (pin "2") (pinfunction "2_2") (pintype "passive"))
      (node (ref "R19") (pin "2") (pinfunction "2_2") (pintype "passive"))
      (node (ref "R20") (pin "2") (pinfunction "2_2") (pintype "passive"))
      (node (ref "R3") (pin "2") (pinfunction "2_2") (pintype "passive"))
      (node (ref "R35") (pin "2") (pinfunction "2_2") (pintype "passive"))
      (node (ref "R4") (pin "2") (pinfunction "2_2") (pintype "passive"))
      (node (ref "R44") (pin "2") (pinfunction "2_2") (pintype "passive"))
      (node (ref "U10") (pin "1") (pinfunction "SENSE+_1") (pintype "open_collector"))
      (node (ref "U11") (pin "1") (pinfunction "SENSE+_1") (pintype "open_collector"))
      (node (ref "U2") (pin "14") (pinfunction "VOS_14") (pintype "bidirectional"))
    )
    (net (code "4") (name "5V_3") (class "Default")
      (node (ref "5V_3") (pin "TESTPOINT") (pinfunction "TESTPOINT_TESTPOINT") (pintype "bidirectional"))
      (node (ref "C27") (pin "2") (pinfunction "2_2") (pintype "bidirectional"))
      (node (ref "L4") (pin "P$2") (pinfunction "2_P$2") (pintype "bidirectional"))
      (node (ref "R24") (pin "2") (pinfunction "2_2") (pintype "passive"))
      (node (ref "R25") (pin "2") (pinfunction "2_2") (pintype "passive"))
      (node (ref "R26") (pin "2") (pinfunction "2_2") (pintype "passive"))
      (node (ref "R27") (pin "2") (pinfunction "2_2") (pintype "passive"))
      (node (ref "R28") (pin "2") (pinfunction "2_2") (pintype "passive"))
      (node (ref "R29") (pin "2") (pinfunction "2_2") (pintype "passive"))
      (node (ref "R36") (pin "2") (pinfunction "2_2") (pintype "passive"))
      (node (ref "R45") (pin "2") (pinfunction "2_2") (pintype "passive"))
      (node (ref "R5") (pin "2") (pinfunction "2_2") (pintype "passive"))
      (node (ref "R6") (pin "2") (pinfunction "2_2") (pintype "passive"))
      (node (ref "U12") (pin "1") (pinfunction "SENSE+_1") (pintype "open_collector"))
      (node (ref "U13") (pin "1") (pinfunction "SENSE+_1") (pintype "open_collector"))
      (node (ref "U4") (pin "14") (pinfunction "VOS_14") (pintype "bidirectional"))
    )
    (net (code "5") (name "5V_4") (class "Default")
      (node (ref "5V_4") (pin "TESTPOINT") (pinfunction "TESTPOINT_TESTPOINT") (pintype "bidirectional"))
      (node (ref "C28") (pin "2") (pinfunction "2_2") (pintype "bidirectional"))
      (node (ref "L5") (pin "P$2") (pinfunction "2_P$2") (pintype "bidirectional"))
      (node (ref "R21") (pin "2") (pinfunction "2_2") (pintype "passive"))
      (node (ref "R22") (pin "2") (pinfunction "2_2") (pintype "passive"))
      (node (ref "R23") (pin "2") (pinfunction "2_2") (pintype "passive"))
      (node (ref "R30") (pin "2") (pinfunction "2_2") (pintype "passive"))
      (node (ref "R31") (pin "2") (pinfunction "2_2") (pintype "passive"))
      (node (ref "R32") (pin "2") (pinfunction "2_2") (pintype "passive"))
      (node (ref "R37") (pin "2") (pinfunction "2_2") (pintype "passive"))
      (node (ref "R46") (pin "2") (pinfunction "2_2") (pintype "passive"))
      (node (ref "R7") (pin "2") (pinfunction "2_2") (pintype "passive"))
      (node (ref "R8") (pin "2") (pinfunction "2_2") (pintype "passive"))
      (node (ref "U14") (pin "1") (pinfunction "SENSE+_1") (pintype "open_collector"))
      (node (ref "U15") (pin "1") (pinfunction "SENSE+_1") (pintype "open_collector"))
      (node (ref "U5") (pin "14") (pinfunction "VOS_14") (pintype "bidirectional"))
    )
    (net (code "6") (name "GND") (class "Default")
      (node (ref "C1") (pin "1") (pinfunction "1_1") (pintype "bidirectional"))
      (node (ref "C10") (pin "2") (pinfunction "2_2") (pintype "bidirectional"))
      (node (ref "C11") (pin "2") (pinfunction "2_2") (pintype "bidirectional"))
      (node (ref "C12") (pin "2") (pinfunction "2_2") (pintype "bidirectional"))
      (node (ref "C13") (pin "2") (pinfunction "2_2") (pintype "bidirectional"))
      (node (ref "C14") (pin "2") (pinfunction "2_2") (pintype "bidirectional"))
      (node (ref "C15") (pin "2") (pinfunction "2_2") (pintype "bidirectional"))
      (node (ref "C16") (pin "2") (pinfunction "2_2") (pintype "bidirectional"))
      (node (ref "C17") (pin "2") (pinfunction "2_2") (pintype "bidirectional"))
      (node (ref "C18") (pin "2") (pinfunction "2_2") (pintype "bidirectional"))
      (node (ref "C19") (pin "P$2") (pinfunction "2_P$2") (pintype "bidirectional"))
      (node (ref "C2") (pin "1") (pinfunction "1_1") (pintype "bidirectional"))
      (node (ref "C20") (pin "P$2") (pinfunction "2_P$2") (pintype "bidirectional"))
      (node (ref "C21") (pin "P$2") (pinfunction "2_P$2") (pintype "bidirectional"))
      (node (ref "C22") (pin "P$2") (pinfunction "2_P$2") (pintype "bidirectional"))
      (node (ref "C23") (pin "P$2") (pinfunction "2_P$2") (pintype "bidirectional"))
      (node (ref "C24") (pin "1") (pinfunction "1_1") (pintype "bidirectional"))
      (node (ref "C25") (pin "1") (pinfunction "1_1") (pintype "bidirectional"))
      (node (ref "C26") (pin "1") (pinfunction "1_1") (pintype "bidirectional"))
      (node (ref "C27") (pin "1") (pinfunction "1_1") (pintype "bidirectional"))
      (node (ref "C28") (pin "1") (pinfunction "1_1") (pintype "bidirectional"))
      (node (ref "C3") (pin "1") (pinfunction "1_1") (pintype "bidirectional"))
      (node (ref "C4") (pin "1") (pinfunction "1_1") (pintype "bidirectional"))
      (node (ref "C5") (pin "1") (pinfunction "1_1") (pintype "bidirectional"))
      (node (ref "C6") (pin "2") (pinfunction "2_2") (pintype "bidirectional"))
      (node (ref "C7") (pin "2") (pinfunction "2_2") (pintype "bidirectional"))
      (node (ref "C8") (pin "2") (pinfunction "2_2") (pintype "bidirectional"))
      (node (ref "C9") (pin "2") (pinfunction "2_2") (pintype "bidirectional"))
      (node (ref "GND") (pin "TESTPOINT") (pinfunction "TESTPOINT_TESTPOINT") (pintype "bidirectional"))
      (node (ref "J1") (pin "1") (pinfunction "GND_1") (pintype "power_in"))
      (node (ref "J1") (pin "18") (pinfunction "VBATT-_18") (pintype "power_in"))
      (node (ref "JP2") (pin "1") (pinfunction "1_1") (pintype "passive"))
      (node (ref "R38") (pin "1") (pinfunction "1_1") (pintype "passive"))
      (node (ref "R39") (pin "1") (pinfunction "1_1") (pintype "passive"))
      (node (ref "R40") (pin "1") (pinfunction "1_1") (pintype "passive"))
      (node (ref "R41") (pin "1") (pinfunction "1_1") (pintype "passive"))
      (node (ref "R42") (pin "1") (pinfunction "1_1") (pintype "passive"))
      (node (ref "U1") (pin "15") (pinfunction "PGND_15") (pintype "bidirectional"))
      (node (ref "U1") (pin "16") (pinfunction "PGND_16") (pintype "bidirectional"))
      (node (ref "U1") (pin "6") (pinfunction "AGND_6") (pintype "bidirectional"))
      (node (ref "U1") (pin "7") (pinfunction "FSW_7") (pintype "bidirectional"))
      (node (ref "U1") (pin "8") (pinfunction "DEF_8") (pintype "bidirectional"))
      (node (ref "U1") (pin "GND") (pinfunction "PGND_GND") (pintype "bidirectional"))
      (node (ref "U10") (pin "2") (pinfunction "GND_2") (pintype "open_collector"))
      (node (ref "U11") (pin "2") (pinfunction "GND_2") (pintype "open_collector"))
      (node (ref "U12") (pin "2") (pinfunction "GND_2") (pintype "open_collector"))
      (node (ref "U13") (pin "2") (pinfunction "GND_2") (pintype "open_collector"))
      (node (ref "U14") (pin "2") (pinfunction "GND_2") (pintype "open_collector"))
      (node (ref "U15") (pin "2") (pinfunction "GND_2") (pintype "open_collector"))
      (node (ref "U2") (pin "15") (pinfunction "PGND_15") (pintype "bidirectional"))
      (node (ref "U2") (pin "16") (pinfunction "PGND_16") (pintype "bidirectional"))
      (node (ref "U2") (pin "6") (pinfunction "AGND_6") (pintype "bidirectional"))
      (node (ref "U2") (pin "7") (pinfunction "FSW_7") (pintype "bidirectional"))
      (node (ref "U2") (pin "8") (pinfunction "DEF_8") (pintype "bidirectional"))
      (node (ref "U2") (pin "GND") (pinfunction "PGND_GND") (pintype "bidirectional"))
      (node (ref "U3") (pin "15") (pinfunction "PGND_15") (pintype "bidirectional"))
      (node (ref "U3") (pin "16") (pinfunction "PGND_16") (pintype "bidirectional"))
      (node (ref "U3") (pin "6") (pinfunction "AGND_6") (pintype "bidirectional"))
      (node (ref "U3") (pin "7") (pinfunction "FSW_7") (pintype "bidirectional"))
      (node (ref "U3") (pin "8") (pinfunction "DEF_8") (pintype "bidirectional"))
      (node (ref "U3") (pin "GND") (pinfunction "PGND_GND") (pintype "bidirectional"))
      (node (ref "U4") (pin "15") (pinfunction "PGND_15") (pintype "bidirectional"))
      (node (ref "U4") (pin "16") (pinfunction "PGND_16") (pintype "bidirectional"))
      (node (ref "U4") (pin "6") (pinfunction "AGND_6") (pintype "bidirectional"))
      (node (ref "U4") (pin "7") (pinfunction "FSW_7") (pintype "bidirectional"))
      (node (ref "U4") (pin "8") (pinfunction "DEF_8") (pintype "bidirectional"))
      (node (ref "U4") (pin "GND") (pinfunction "PGND_GND") (pintype "bidirectional"))
      (node (ref "U5") (pin "15") (pinfunction "PGND_15") (pintype "bidirectional"))
      (node (ref "U5") (pin "16") (pinfunction "PGND_16") (pintype "bidirectional"))
      (node (ref "U5") (pin "6") (pinfunction "AGND_6") (pintype "bidirectional"))
      (node (ref "U5") (pin "7") (pinfunction "FSW_7") (pintype "bidirectional"))
      (node (ref "U5") (pin "8") (pinfunction "DEF_8") (pintype "bidirectional"))
      (node (ref "U5") (pin "GND") (pinfunction "PGND_GND") (pintype "bidirectional"))
      (node (ref "U6") (pin "1") (pinfunction "A0_1") (pintype "bidirectional"))
      (node (ref "U6") (pin "10") (pinfunction "GND_10") (pintype "bidirectional"))
      (node (ref "U6") (pin "2") (pinfunction "A1_2") (pintype "bidirectional"))
      (node (ref "U6") (pin "3") (pinfunction "A2_3") (pintype "bidirectional"))
      (node (ref "U7") (pin "10") (pinfunction "GND_10") (pintype "bidirectional"))
      (node (ref "U7") (pin "2") (pinfunction "A1_2") (pintype "bidirectional"))
      (node (ref "U7") (pin "3") (pinfunction "A2_3") (pintype "bidirectional"))
      (node (ref "U8") (pin "2") (pinfunction "GND_2") (pintype "open_collector"))
      (node (ref "U9") (pin "2") (pinfunction "GND_2") (pintype "open_collector"))
    )
    (net (code "7") (name "Net-(L1-1)") (class "Default")
      (node (ref "L1") (pin "P$1") (pinfunction "1_P$1") (pintype "bidirectional"))
      (node (ref "U1") (pin "1") (pinfunction "SW_1") (pintype "bidirectional"))
      (node (ref "U1") (pin "2") (pinfunction "SW_2") (pintype "bidirectional"))
      (node (ref "U1") (pin "3") (pinfunction "SW_3") (pintype "bidirectional"))
    )
    (net (code "8") (name "Net-(L2-1)") (class "Default")
      (node (ref "L2") (pin "P$1") (pinfunction "1_P$1") (pintype "bidirectional"))
      (node (ref "U2") (pin "1") (pinfunction "SW_1") (pintype "bidirectional"))
      (node (ref "U2") (pin "2") (pinfunction "SW_2") (pintype "bidirectional"))
      (node (ref "U2") (pin "3") (pinfunction "SW_3") (pintype "bidirectional"))
    )
    (net (code "9") (name "Net-(L3-1)") (class "Default")
      (node (ref "L3") (pin "P$1") (pinfunction "1_P$1") (pintype "bidirectional"))
      (node (ref "U3") (pin "1") (pinfunction "SW_1") (pintype "bidirectional"))
      (node (ref "U3") (pin "2") (pinfunction "SW_2") (pintype "bidirectional"))
      (node (ref "U3") (pin "3") (pinfunction "SW_3") (pintype "bidirectional"))
    )
    (net (code "10") (name "Net-(L4-1)") (class "Default")
      (node (ref "L4") (pin "P$1") (pinfunction "1_P$1") (pintype "bidirectional"))
      (node (ref "U4") (pin "1") (pinfunction "SW_1") (pintype "bidirectional"))
      (node (ref "U4") (pin "2") (pinfunction "SW_2") (pintype "bidirectional"))
      (node (ref "U4") (pin "3") (pinfunction "SW_3") (pintype "bidirectional"))
    )
    (net (code "11") (name "Net-(L5-1)") (class "Default")
      (node (ref "L5") (pin "P$1") (pinfunction "1_P$1") (pintype "bidirectional"))
      (node (ref "U5") (pin "1") (pinfunction "SW_1") (pintype "bidirectional"))
      (node (ref "U5") (pin "2") (pinfunction "SW_2") (pintype "bidirectional"))
      (node (ref "U5") (pin "3") (pinfunction "SW_3") (pintype "bidirectional"))
    )
    (net (code "12") (name "Net-(U1-FB)") (class "Default")
      (node (ref "R42") (pin "2") (pinfunction "2_2") (pintype "passive"))
      (node (ref "R47") (pin "1") (pinfunction "1_1") (pintype "passive"))
      (node (ref "U1") (pin "5") (pinfunction "FB_5") (pintype "bidirectional"))
    )
    (net (code "13") (name "Net-(U1-PG)") (class "Default")
      (node (ref "R33") (pin "1") (pinfunction "1_1") (pintype "passive"))
      (node (ref "U1") (pin "4") (pinfunction "PG_4") (pintype "bidirectional"))
    )
    (net (code "14") (name "Net-(U1-SS{slash}TR)") (class "Default")
      (node (ref "C1") (pin "2") (pinfunction "2_2") (pintype "bidirectional"))
      (node (ref "U1") (pin "9") (pinfunction "SS/TR_9") (pintype "bidirectional"))
    )
    (net (code "15") (name "Net-(U2-FB)") (class "Default")
      (node (ref "R39") (pin "2") (pinfunction "2_2") (pintype "passive"))
      (node (ref "R44") (pin "1") (pinfunction "1_1") (pintype "passive"))
      (node (ref "U2") (pin "5") (pinfunction "FB_5") (pintype "bidirectional"))
    )
    (net (code "16") (name "Net-(U2-PG)") (class "Default")
      (node (ref "R35") (pin "1") (pinfunction "1_1") (pintype "passive"))
      (node (ref "U2") (pin "4") (pinfunction "PG_4") (pintype "bidirectional"))
    )
    (net (code "17") (name "Net-(U2-SS{slash}TR)") (class "Default")
      (node (ref "C2") (pin "2") (pinfunction "2_2") (pintype "bidirectional"))
      (node (ref "U2") (pin "9") (pinfunction "SS/TR_9") (pintype "bidirectional"))
    )
    (net (code "18") (name "Net-(U3-FB)") (class "Default")
      (node (ref "R38") (pin "2") (pinfunction "2_2") (pintype "passive"))
      (node (ref "R43") (pin "1") (pinfunction "1_1") (pintype "passive"))
      (node (ref "U3") (pin "5") (pinfunction "FB_5") (pintype "bidirectional"))
    )
    (net (code "19") (name "Net-(U3-PG)") (class "Default")
      (node (ref "R34") (pin "1") (pinfunction "1_1") (pintype "passive"))
      (node (ref "U3") (pin "4") (pinfunction "PG_4") (pintype "bidirectional"))
    )
    (net (code "20") (name "Net-(U3-SS{slash}TR)") (class "Default")
      (node (ref "C3") (pin "2") (pinfunction "2_2") (pintype "bidirectional"))
      (node (ref "U3") (pin "9") (pinfunction "SS/TR_9") (pintype "bidirectional"))
    )
    (net (code "21") (name "Net-(U4-FB)") (class "Default")
      (node (ref "R40") (pin "2") (pinfunction "2_2") (pintype "passive"))
      (node (ref "R45") (pin "1") (pinfunction "1_1") (pintype "passive"))
      (node (ref "U4") (pin "5") (pinfunction "FB_5") (pintype "bidirectional"))
    )
    (net (code "22") (name "Net-(U4-PG)") (class "Default")
      (node (ref "R36") (pin "1") (pinfunction "1_1") (pintype "passive"))
      (node (ref "U4") (pin "4") (pinfunction "PG_4") (pintype "bidirectional"))
    )
    (net (code "23") (name "Net-(U4-SS{slash}TR)") (class "Default")
      (node (ref "C4") (pin "2") (pinfunction "2_2") (pintype "bidirectional"))
      (node (ref "U4") (pin "9") (pinfunction "SS/TR_9") (pintype "bidirectional"))
    )
    (net (code "24") (name "Net-(U5-FB)") (class "Default")
      (node (ref "R41") (pin "2") (pinfunction "2_2") (pintype "passive"))
      (node (ref "R46") (pin "1") (pinfunction "1_1") (pintype "passive"))
      (node (ref "U5") (pin "5") (pinfunction "FB_5") (pintype "bidirectional"))
    )
    (net (code "25") (name "Net-(U5-PG)") (class "Default")
      (node (ref "R37") (pin "1") (pinfunction "1_1") (pintype "passive"))
      (node (ref "U5") (pin "4") (pinfunction "PG_4") (pintype "bidirectional"))
    )
    (net (code "26") (name "Net-(U5-SS{slash}TR)") (class "Default")
      (node (ref "C5") (pin "2") (pinfunction "2_2") (pintype "bidirectional"))
      (node (ref "U5") (pin "9") (pinfunction "SS/TR_9") (pintype "bidirectional"))
    )
    (net (code "27") (name "Net-(U6-SC0)") (class "Default")
      (node (ref "R10") (pin "1") (pinfunction "1_1") (pintype "passive"))
      (node (ref "U6") (pin "6") (pinfunction "SC0_6") (pintype "bidirectional"))
      (node (ref "U8") (pin "3") (pinfunction "SCL_3") (pintype "open_collector"))
    )
    (net (code "28") (name "Net-(U6-SC1)") (class "Default")
      (node (ref "R13") (pin "1") (pinfunction "1_1") (pintype "passive"))
      (node (ref "U6") (pin "9") (pinfunction "SC1_9") (pintype "bidirectional"))
      (node (ref "U9") (pin "3") (pinfunction "SCL_3") (pintype "open_collector"))
    )
    (net (code "29") (name "Net-(U6-SD0)") (class "Default")
      (node (ref "R9") (pin "1") (pinfunction "1_1") (pintype "passive"))
      (node (ref "U6") (pin "5") (pinfunction "SD0_5") (pintype "bidirectional"))
      (node (ref "U8") (pin "4") (pinfunction "SDA_4") (pintype "open_collector"))
    )
    (net (code "30") (name "Net-(U6-SD1)") (class "Default")
      (node (ref "R12") (pin "1") (pinfunction "1_1") (pintype "passive"))
      (node (ref "U6") (pin "8") (pinfunction "SD1_8") (pintype "bidirectional"))
      (node (ref "U9") (pin "4") (pinfunction "SDA_4") (pintype "open_collector"))
    )
    (net (code "31") (name "Net-(U6-~{INT0})") (class "Default")
      (node (ref "R11") (pin "1") (pinfunction "1_1") (pintype "passive"))
      (node (ref "U6") (pin "4") (pinfunction "~{INT0}_4") (pintype "bidirectional"))
      (node (ref "U8") (pin "5") (pinfunction "~{ALERT}_5") (pintype "open_collector"))
    )
    (net (code "32") (name "Net-(U6-~{INT1})") (class "Default")
      (node (ref "R14") (pin "1") (pinfunction "1_1") (pintype "passive"))
      (node (ref "U6") (pin "7") (pinfunction "~{INT1}_7") (pintype "bidirectional"))
      (node (ref "U9") (pin "5") (pinfunction "~{ALERT}_5") (pintype "open_collector"))
    )
    (net (code "33") (name "Net-(U10-SCL)") (class "Default")
      (node (ref "R16") (pin "1") (pinfunction "1_1") (pintype "passive"))
      (node (ref "U10") (pin "3") (pinfunction "SCL_3") (pintype "open_collector"))
      (node (ref "U6") (pin "13") (pinfunction "SC2_13") (pintype "bidirectional"))
    )
    (net (code "34") (name "Net-(U10-SDA)") (class "Default")
      (node (ref "R15") (pin "1") (pinfunction "1_1") (pintype "passive"))
      (node (ref "U10") (pin "4") (pinfunction "SDA_4") (pintype "open_collector"))
      (node (ref "U6") (pin "12") (pinfunction "SD2_12") (pintype "bidirectional"))
    )
    (net (code "35") (name "Net-(U10-~{ALERT})") (class "Default")
      (node (ref "R17") (pin "1") (pinfunction "1_1") (pintype "passive"))
      (node (ref "U10") (pin "5") (pinfunction "~{ALERT}_5") (pintype "open_collector"))
      (node (ref "U6") (pin "11") (pinfunction "~{INT2}_11") (pintype "bidirectional"))
    )
    (net (code "36") (name "Net-(U11-SCL)") (class "Default")
      (node (ref "R19") (pin "1") (pinfunction "1_1") (pintype "passive"))
      (node (ref "U11") (pin "3") (pinfunction "SCL_3") (pintype "open_collector"))
      (node (ref "U6") (pin "16") (pinfunction "SC3_16") (pintype "bidirectional"))
    )
    (net (code "37") (name "Net-(U11-SDA)") (class "Default")
      (node (ref "R18") (pin "1") (pinfunction "1_1") (pintype "passive"))
      (node (ref "U11") (pin "4") (pinfunction "SDA_4") (pintype "open_collector"))
      (node (ref "U6") (pin "15") (pinfunction "SD3_15") (pintype "bidirectional"))
    )
    (net (code "38") (name "Net-(U11-~{ALERT})") (class "Default")
      (node (ref "R20") (pin "1") (pinfunction "1_1") (pintype "passive"))
      (node (ref "U11") (pin "5") (pinfunction "~{ALERT}_5") (pintype "open_collector"))
      (node (ref "U6") (pin "14") (pinfunction "~{INT3}_14") (pintype "bidirectional"))
    )
    (net (code "39") (name "Net-(U12-SCL)") (class "Default")
      (node (ref "R28") (pin "1") (pinfunction "1_1") (pintype "passive"))
      (node (ref "U12") (pin "3") (pinfunction "SCL_3") (pintype "open_collector"))
      (node (ref "U7") (pin "6") (pinfunction "SC0_6") (pintype "bidirectional"))
    )
    (net (code "40") (name "Net-(U12-SDA)") (class "Default")
      (node (ref "R27") (pin "1") (pinfunction "1_1") (pintype "passive"))
      (node (ref "U12") (pin "4") (pinfunction "SDA_4") (pintype "open_collector"))
      (node (ref "U7") (pin "5") (pinfunction "SD0_5") (pintype "bidirectional"))
    )
    (net (code "41") (name "Net-(U12-~{ALERT})") (class "Default")
      (node (ref "R29") (pin "1") (pinfunction "1_1") (pintype "passive"))
      (node (ref "U12") (pin "5") (pinfunction "~{ALERT}_5") (pintype "open_collector"))
      (node (ref "U7") (pin "4") (pinfunction "~{INT0}_4") (pintype "bidirectional"))
    )
    (net (code "42") (name "Net-(U13-SCL)") (class "Default")
      (node (ref "R25") (pin "1") (pinfunction "1_1") (pintype "passive"))
      (node (ref "U13") (pin "3") (pinfunction "SCL_3") (pintype "open_collector"))
      (node (ref "U7") (pin "9") (pinfunction "SC1_9") (pintype "bidirectional"))
    )
    (net (code "43") (name "Net-(U13-SDA)") (class "Default")
      (node (ref "R24") (pin "1") (pinfunction "1_1") (pintype "passive"))
      (node (ref "U13") (pin "4") (pinfunction "SDA_4") (pintype "open_collector"))
      (node (ref "U7") (pin "8") (pinfunction "SD1_8") (pintype "bidirectional"))
    )
    (net (code "44") (name "Net-(U13-~{ALERT})") (class "Default")
      (node (ref "R26") (pin "1") (pinfunction "1_1") (pintype "passive"))
      (node (ref "U13") (pin "5") (pinfunction "~{ALERT}_5") (pintype "open_collector"))
      (node (ref "U7") (pin "7") (pinfunction "~{INT1}_7") (pintype "bidirectional"))
    )
    (net (code "45") (name "Net-(U14-SCL)") (class "Default")
      (node (ref "R22") (pin "1") (pinfunction "1_1") (pintype "passive"))
      (node (ref "U14") (pin "3") (pinfunction "SCL_3") (pintype "open_collector"))
      (node (ref "U7") (pin "13") (pinfunction "SC2_13") (pintype "bidirectional"))
    )
    (net (code "46") (name "Net-(U14-SDA)") (class "Default")
      (node (ref "R21") (pin "1") (pinfunction "1_1") (pintype "passive"))
      (node (ref "U14") (pin "4") (pinfunction "SDA_4") (pintype "open_collector"))
      (node (ref "U7") (pin "12") (pinfunction "SD2_12") (pintype "bidirectional"))
    )
    (net (code "47") (name "Net-(U14-~{ALERT})") (class "Default")
      (node (ref "R23") (pin "1") (pinfunction "1_1") (pintype "passive"))
      (node (ref "U14") (pin "5") (pinfunction "~{ALERT}_5") (pintype "open_collector"))
      (node (ref "U7") (pin "11") (pinfunction "~{INT2}_11") (pintype "bidirectional"))
    )
    (net (code "48") (name "Net-(U15-SCL)") (class "Default")
      (node (ref "R31") (pin "1") (pinfunction "1_1") (pintype "passive"))
      (node (ref "U15") (pin "3") (pinfunction "SCL_3") (pintype "open_collector"))
      (node (ref "U7") (pin "16") (pinfunction "SC3_16") (pintype "bidirectional"))
    )
    (net (code "49") (name "Net-(U15-SDA)") (class "Default")
      (node (ref "R30") (pin "1") (pinfunction "1_1") (pintype "passive"))
      (node (ref "U15") (pin "4") (pinfunction "SDA_4") (pintype "open_collector"))
      (node (ref "U7") (pin "15") (pinfunction "SD3_15") (pintype "bidirectional"))
    )
    (net (code "50") (name "Net-(U15-~{ALERT})") (class "Default")
      (node (ref "R32") (pin "1") (pinfunction "1_1") (pintype "passive"))
      (node (ref "U15") (pin "5") (pinfunction "~{ALERT}_5") (pintype "open_collector"))
      (node (ref "U7") (pin "14") (pinfunction "~{INT3}_14") (pintype "bidirectional"))
    )
    (net (code "51") (name "SCL") (class "Default")
      (node (ref "J1") (pin "5") (pinfunction "SMBCLK_5") (pintype "open_collector"))
      (node (ref "SCL") (pin "TESTPOINT") (pinfunction "TESTPOINT_TESTPOINT") (pintype "bidirectional"))
      (node (ref "U6") (pin "18") (pinfunction "SCL_18") (pintype "bidirectional"))
      (node (ref "U7") (pin "18") (pinfunction "SCL_18") (pintype "bidirectional"))
    )
    (net (code "52") (name "SDA") (class "Default")
      (node (ref "J1") (pin "3") (pinfunction "SMBDATA_3") (pintype "open_collector"))
      (node (ref "SDA") (pin "TESTPOINT") (pinfunction "TESTPOINT_TESTPOINT") (pintype "bidirectional"))
      (node (ref "U6") (pin "19") (pinfunction "SDA_19") (pintype "bidirectional"))
      (node (ref "U7") (pin "19") (pinfunction "SDA_19") (pintype "bidirectional"))
    )
    (net (code "53") (name "VBATT") (class "Default")
      (node (ref "C10") (pin "1") (pinfunction "1_1") (pintype "bidirectional"))
      (node (ref "C19") (pin "P$1") (pinfunction "1_P$1") (pintype "bidirectional"))
      (node (ref "C20") (pin "P$1") (pinfunction "1_P$1") (pintype "bidirectional"))
      (node (ref "C21") (pin "P$1") (pinfunction "1_P$1") (pintype "bidirectional"))
      (node (ref "C22") (pin "P$1") (pinfunction "1_P$1") (pintype "bidirectional"))
      (node (ref "C23") (pin "P$1") (pinfunction "1_P$1") (pintype "bidirectional"))
      (node (ref "C6") (pin "1") (pinfunction "1_1") (pintype "bidirectional"))
      (node (ref "C7") (pin "1") (pinfunction "1_1") (pintype "bidirectional"))
      (node (ref "C8") (pin "1") (pinfunction "1_1") (pintype "bidirectional"))
      (node (ref "C9") (pin "1") (pinfunction "1_1") (pintype "bidirectional"))
      (node (ref "J1") (pin "17") (pinfunction "VBATT+_17") (pintype "power_in"))
      (node (ref "JP2") (pin "2") (pinfunction "2_2") (pintype "passive"))
      (node (ref "U1") (pin "10") (pinfunction "AVIN_10") (pintype "bidirectional"))
      (node (ref "U1") (pin "11") (pinfunction "PVIN_11") (pintype "bidirectional"))
      (node (ref "U1") (pin "12") (pinfunction "PVIN_12") (pintype "bidirectional"))
      (node (ref "U1") (pin "13") (pinfunction "EN_13") (pintype "bidirectional"))
      (node (ref "U2") (pin "10") (pinfunction "AVIN_10") (pintype "bidirectional"))
      (node (ref "U2") (pin "11") (pinfunction "PVIN_11") (pintype "bidirectional"))
      (node (ref "U2") (pin "12") (pinfunction "PVIN_12") (pintype "bidirectional"))
      (node (ref "U2") (pin "13") (pinfunction "EN_13") (pintype "bidirectional"))
      (node (ref "U3") (pin "10") (pinfunction "AVIN_10") (pintype "bidirectional"))
      (node (ref "U3") (pin "11") (pinfunction "PVIN_11") (pintype "bidirectional"))
      (node (ref "U3") (pin "12") (pinfunction "PVIN_12") (pintype "bidirectional"))
      (node (ref "U3") (pin "13") (pinfunction "EN_13") (pintype "bidirectional"))
      (node (ref "U4") (pin "10") (pinfunction "AVIN_10") (pintype "bidirectional"))
      (node (ref "U4") (pin "11") (pinfunction "PVIN_11") (pintype "bidirectional"))
      (node (ref "U4") (pin "12") (pinfunction "PVIN_12") (pintype "bidirectional"))
      (node (ref "U4") (pin "13") (pinfunction "EN_13") (pintype "bidirectional"))
      (node (ref "U5") (pin "10") (pinfunction "AVIN_10") (pintype "bidirectional"))
      (node (ref "U5") (pin "11") (pinfunction "PVIN_11") (pintype "bidirectional"))
      (node (ref "U5") (pin "12") (pinfunction "PVIN_12") (pintype "bidirectional"))
      (node (ref "U5") (pin "13") (pinfunction "EN_13") (pintype "bidirectional"))
      (node (ref "VBATT") (pin "TESTPOINT") (pinfunction "TESTPOINT_TESTPOINT") (pintype "bidirectional"))
    )
    (net (code "54") (name "VCC_BACKPLANE") (class "Default")
      (node (ref "BACK") (pin "TESTPOINT") (pinfunction "TESTPOINT_TESTPOINT") (pintype "bidirectional"))
      (node (ref "C11") (pin "1") (pinfunction "1_1") (pintype "bidirectional"))
      (node (ref "J1") (pin "13") (pinfunction "VCC_BACKPLANE_13") (pintype "power_in"))
      (node (ref "J1") (pin "2") (pinfunction "VCC_CONTROLLER_2") (pintype "power_in"))
      (node (ref "R1") (pin "1") (pinfunction "1_1") (pintype "passive"))
      (node (ref "U6") (pin "20") (pinfunction "VCC_20") (pintype "bidirectional"))
      (node (ref "U7") (pin "1") (pinfunction "A0_1") (pintype "bidirectional"))
      (node (ref "U7") (pin "20") (pinfunction "VCC_20") (pintype "bidirectional"))
      (node (ref "U8") (pin "6") (pinfunction "SENSE-_6") (pintype "open_collector"))
    )
    (net (code "55") (name "VCC_LINUX") (class "Default")
      (node (ref "C12") (pin "1") (pinfunction "1_1") (pintype "bidirectional"))
      (node (ref "J1") (pin "4") (pinfunction "VCC_LINUX_4") (pintype "power_in"))
      (node (ref "LINUX") (pin "TESTPOINT") (pinfunction "TESTPOINT_TESTPOINT") (pintype "bidirectional"))
      (node (ref "R2") (pin "1") (pinfunction "1_1") (pintype "passive"))
      (node (ref "U9") (pin "6") (pinfunction "SENSE-_6") (pintype "open_collector"))
    )
    (net (code "56") (name "VCC_MOD0") (class "Default")
      (node (ref "C13") (pin "1") (pinfunction "1_1") (pintype "bidirectional"))
      (node (ref "J1") (pin "7") (pinfunction "VCC_MOD0_7") (pintype "power_in"))
      (node (ref "MOD0") (pin "TESTPOINT") (pinfunction "TESTPOINT_TESTPOINT") (pintype "bidirectional"))
      (node (ref "R3") (pin "1") (pinfunction "1_1") (pintype "passive"))
      (node (ref "U10") (pin "6") (pinfunction "SENSE-_6") (pintype "open_collector"))
    )
    (net (code "57") (name "VCC_MOD1") (class "Default")
      (node (ref "C14") (pin "1") (pinfunction "1_1") (pintype "bidirectional"))
      (node (ref "J1") (pin "8") (pinfunction "VCC_MOD1_8") (pintype "power_in"))
      (node (ref "MOD1") (pin "TESTPOINT") (pinfunction "TESTPOINT_TESTPOINT") (pintype "bidirectional"))
      (node (ref "R4") (pin "1") (pinfunction "1_1") (pintype "passive"))
      (node (ref "U11") (pin "6") (pinfunction "SENSE-_6") (pintype "open_collector"))
    )
    (net (code "58") (name "VCC_MOD2") (class "Default")
      (node (ref "C15") (pin "1") (pinfunction "1_1") (pintype "bidirectional"))
      (node (ref "J1") (pin "9") (pinfunction "VCC_MOD2_9") (pintype "power_in"))
      (node (ref "MOD2") (pin "TESTPOINT") (pinfunction "TESTPOINT_TESTPOINT") (pintype "bidirectional"))
      (node (ref "R5") (pin "1") (pinfunction "1_1") (pintype "passive"))
      (node (ref "U12") (pin "6") (pinfunction "SENSE-_6") (pintype "open_collector"))
    )
    (net (code "59") (name "VCC_MOD5") (class "Default")
      (node (ref "C16") (pin "1") (pinfunction "1_1") (pintype "bidirectional"))
      (node (ref "J1") (pin "10") (pinfunction "VCC_MOD5_10") (pintype "power_in"))
      (node (ref "MOD5") (pin "TESTPOINT") (pinfunction "TESTPOINT_TESTPOINT") (pintype "bidirectional"))
      (node (ref "R6") (pin "1") (pinfunction "1_1") (pintype "passive"))
      (node (ref "U13") (pin "6") (pinfunction "SENSE-_6") (pintype "open_collector"))
    )
    (net (code "60") (name "VCC_MOD6") (class "Default")
      (node (ref "C17") (pin "1") (pinfunction "1_1") (pintype "bidirectional"))
      (node (ref "J1") (pin "11") (pinfunction "VCC_MOD6_11") (pintype "power_in"))
      (node (ref "MOD6") (pin "TESTPOINT") (pinfunction "TESTPOINT_TESTPOINT") (pintype "bidirectional"))
      (node (ref "R7") (pin "1") (pinfunction "1_1") (pintype "passive"))
      (node (ref "U14") (pin "6") (pinfunction "SENSE-_6") (pintype "open_collector"))
    )
    (net (code "61") (name "VCC_MOD7") (class "Default")
      (node (ref "C18") (pin "1") (pinfunction "1_1") (pintype "bidirectional"))
      (node (ref "J1") (pin "12") (pinfunction "VCC_MOD7_12") (pintype "power_in"))
      (node (ref "MOD7") (pin "TESTPOINT") (pinfunction "TESTPOINT_TESTPOINT") (pintype "bidirectional"))
      (node (ref "R8") (pin "1") (pinfunction "1_1") (pintype "passive"))
      (node (ref "U15") (pin "6") (pinfunction "SENSE-_6") (pintype "open_collector"))
    )
    (net (code "62") (name "VSOL+") (class "Default")
      (node (ref "J1") (pin "19") (pinfunction "VSOL+_19") (pintype "power_in"))
      (node (ref "JP1") (pin "2") (pinfunction "2_2") (pintype "passive"))
      (node (ref "VSOL+") (pin "TESTPOINT") (pinfunction "TESTPOINT_TESTPOINT") (pintype "bidirectional"))
    )
    (net (code "63") (name "VSOL-") (class "Default")
      (node (ref "J1") (pin "20") (pinfunction "VSOL-_20") (pintype "power_in"))
      (node (ref "JP1") (pin "1") (pinfunction "1_1") (pintype "passive"))
      (node (ref "VSOL-") (pin "TESTPOINT") (pinfunction "TESTPOINT_TESTPOINT") (pintype "bidirectional"))
    )
    (net (code "64") (name "~{INT}") (class "Default")
      (node (ref "!INT") (pin "TESTPOINT") (pinfunction "TESTPOINT_TESTPOINT") (pintype "bidirectional"))
      (node (ref "J1") (pin "6") (pinfunction "~{SMBALERT}_6") (pintype "bidirectional"))
      (node (ref "U6") (pin "17") (pinfunction "~{INT}_17") (pintype "bidirectional"))
      (node (ref "U7") (pin "17") (pinfunction "~{INT}_17") (pintype "bidirectional"))
    )
  )
)
